# dram.net
KiCad netlist of a schematic drawn in Altium Designer
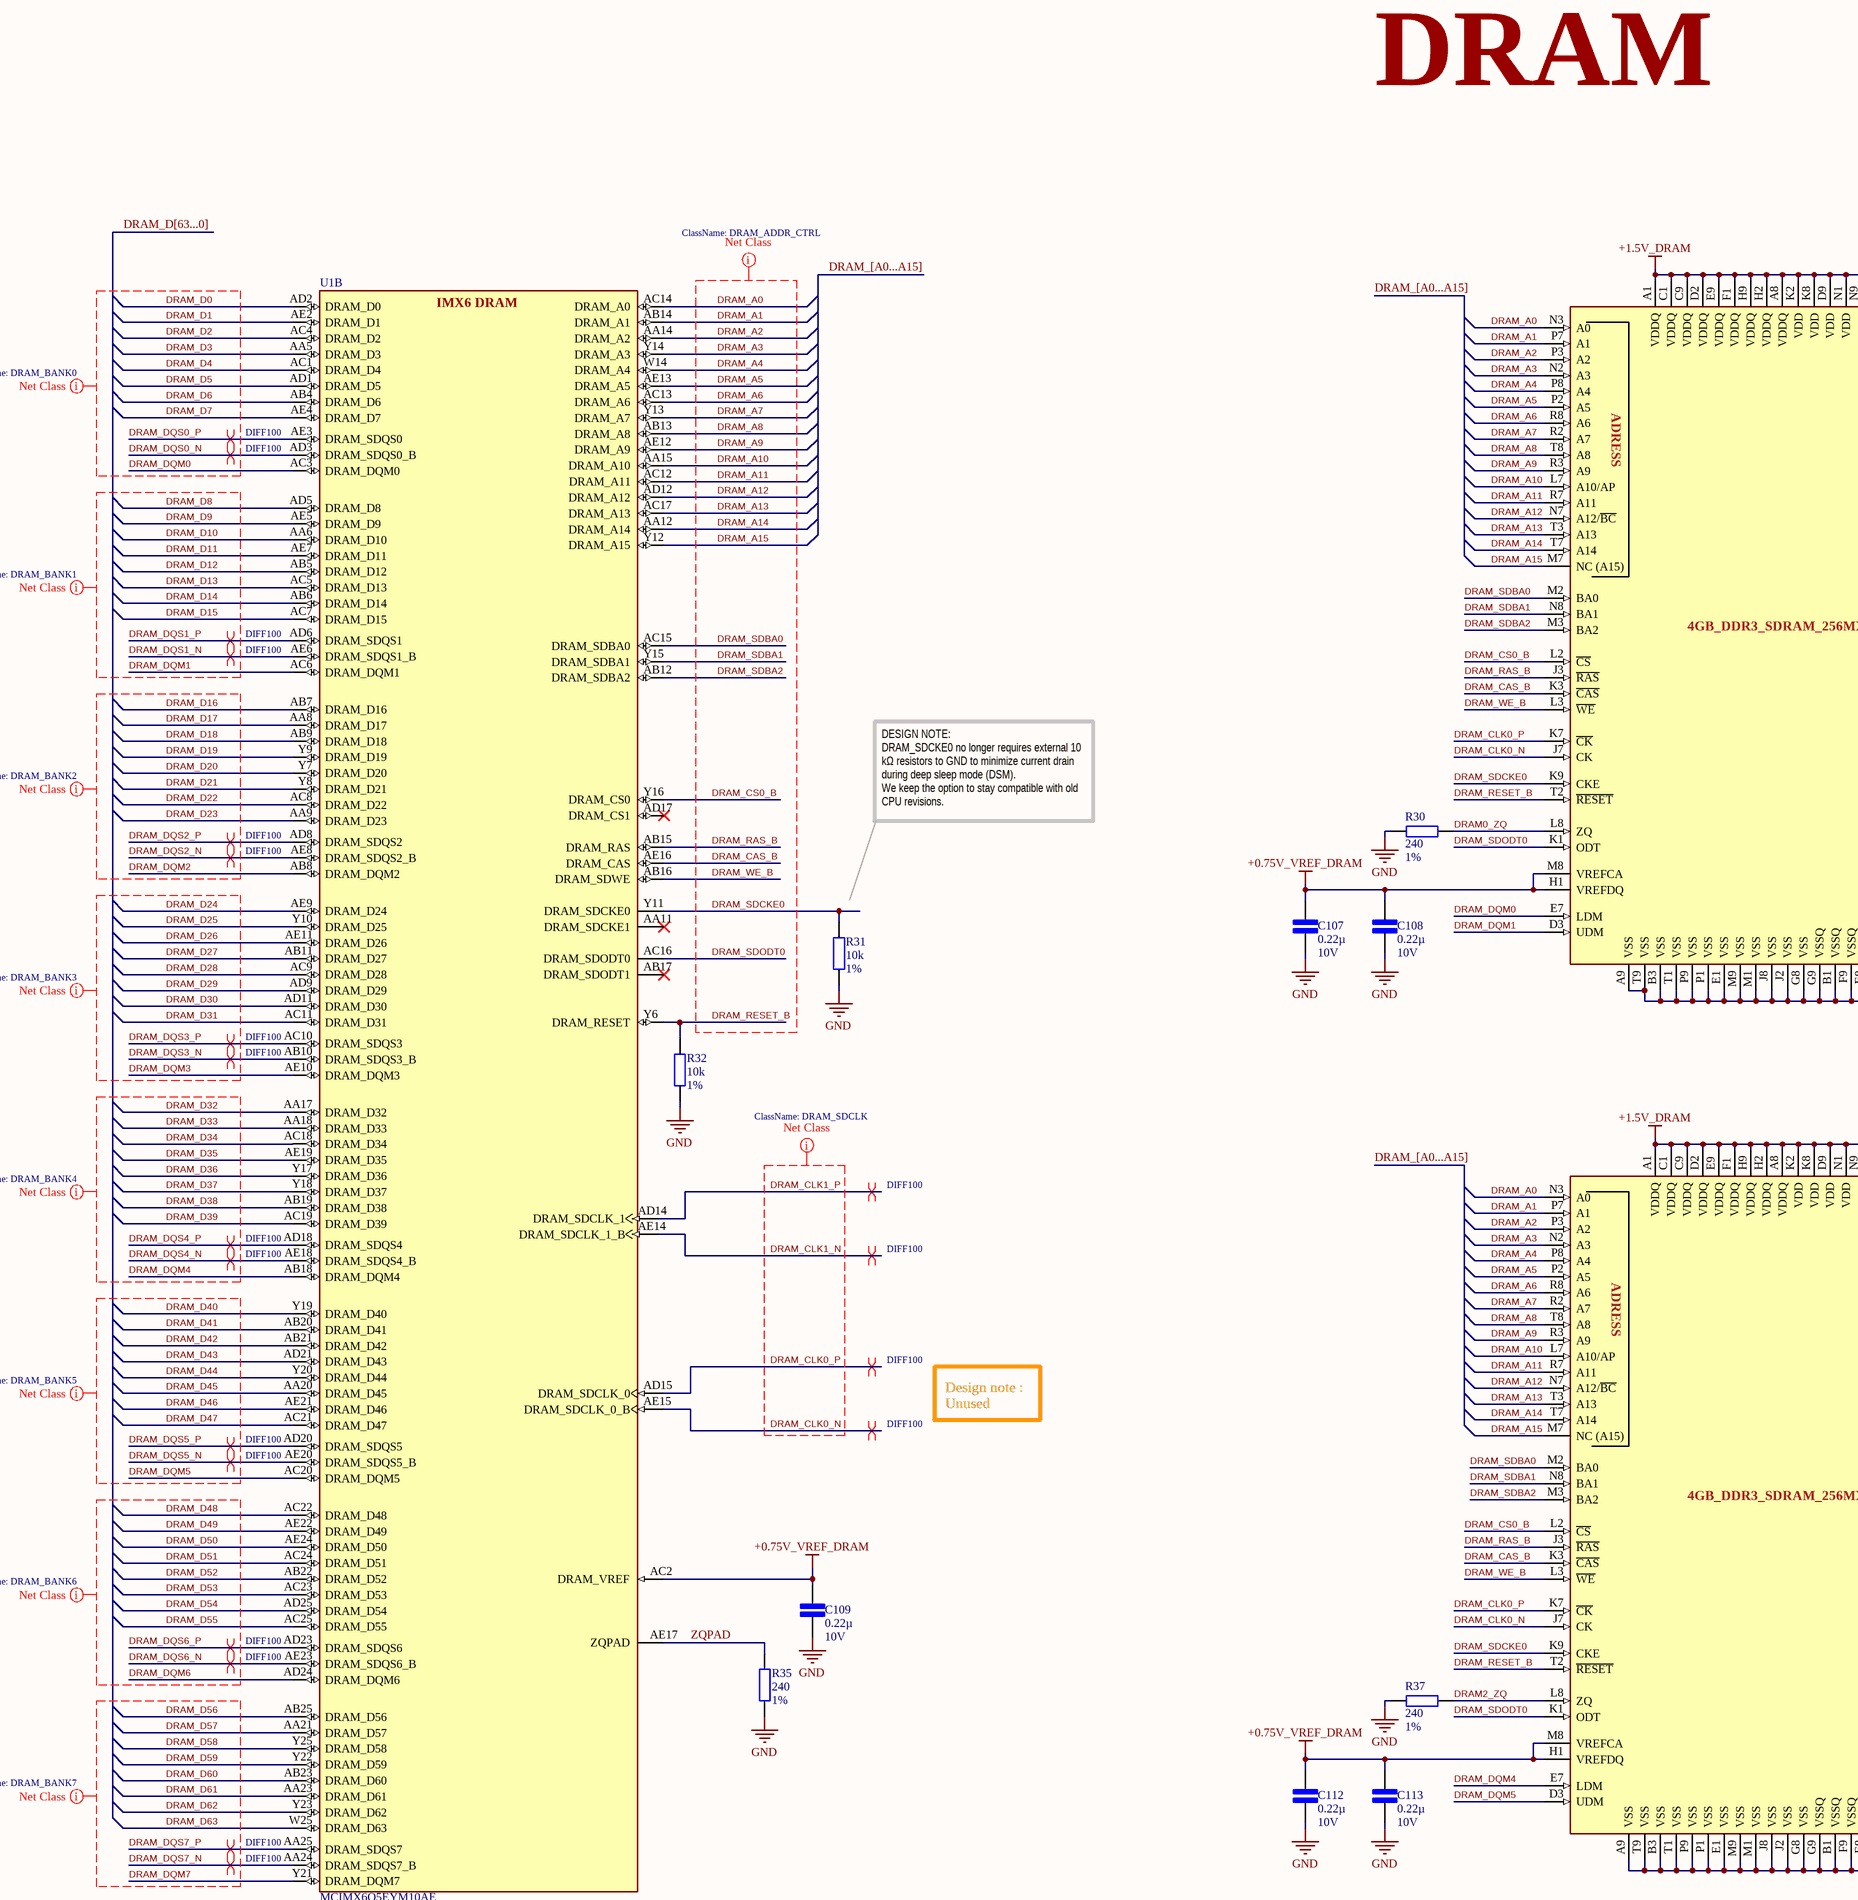
[diagram p0: dram.SchDoc, top left]
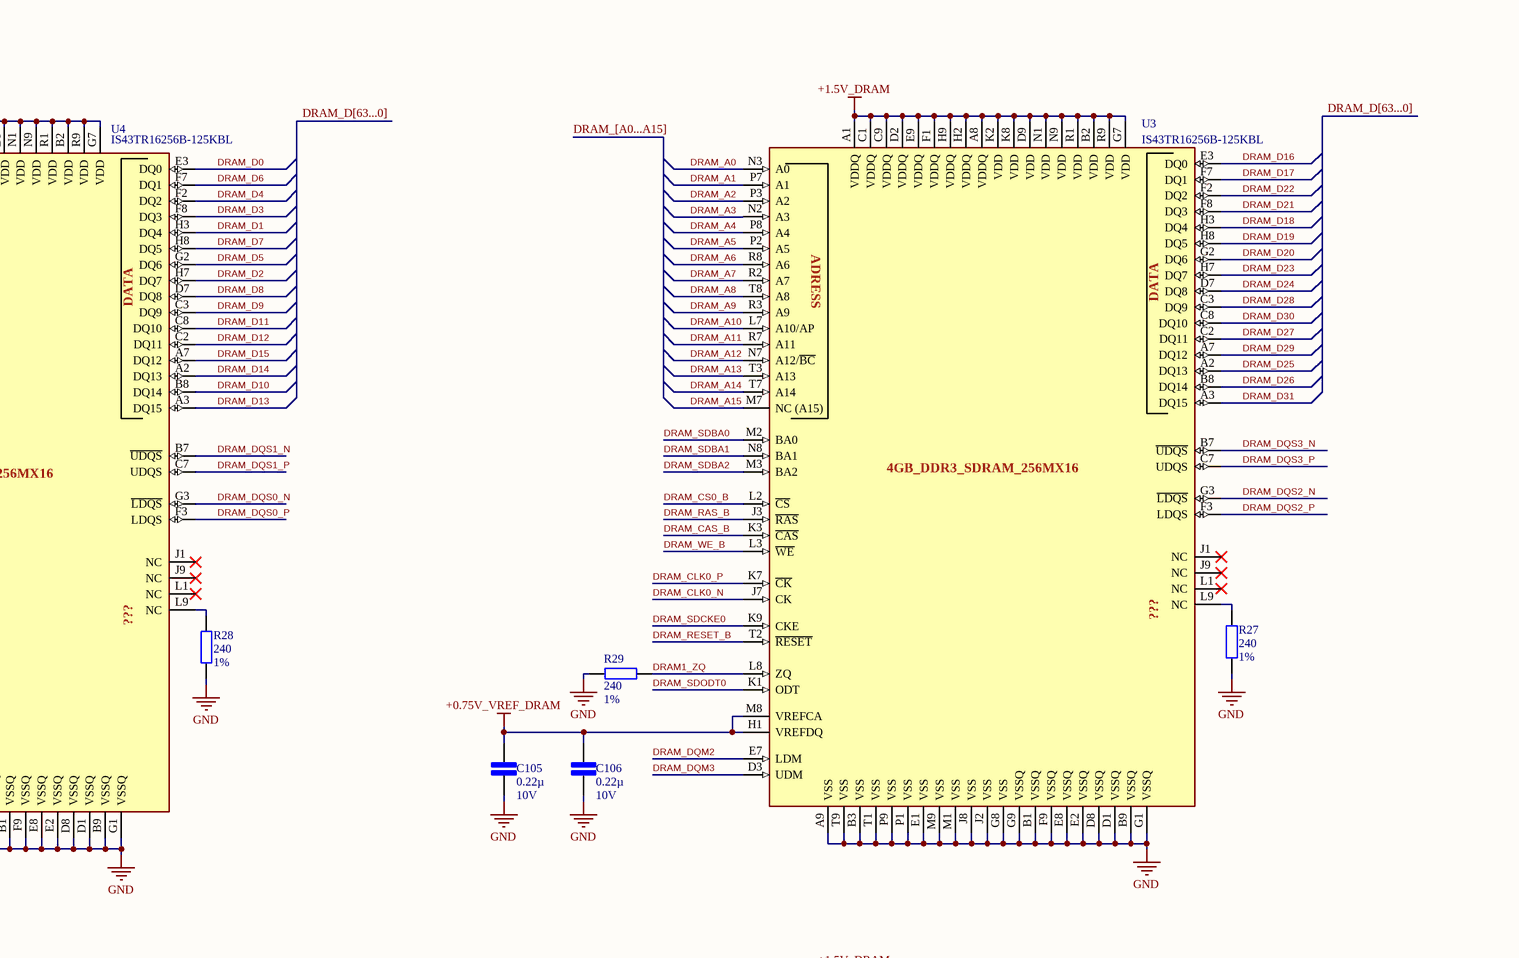
[diagram p1: dram.SchDoc, top right]
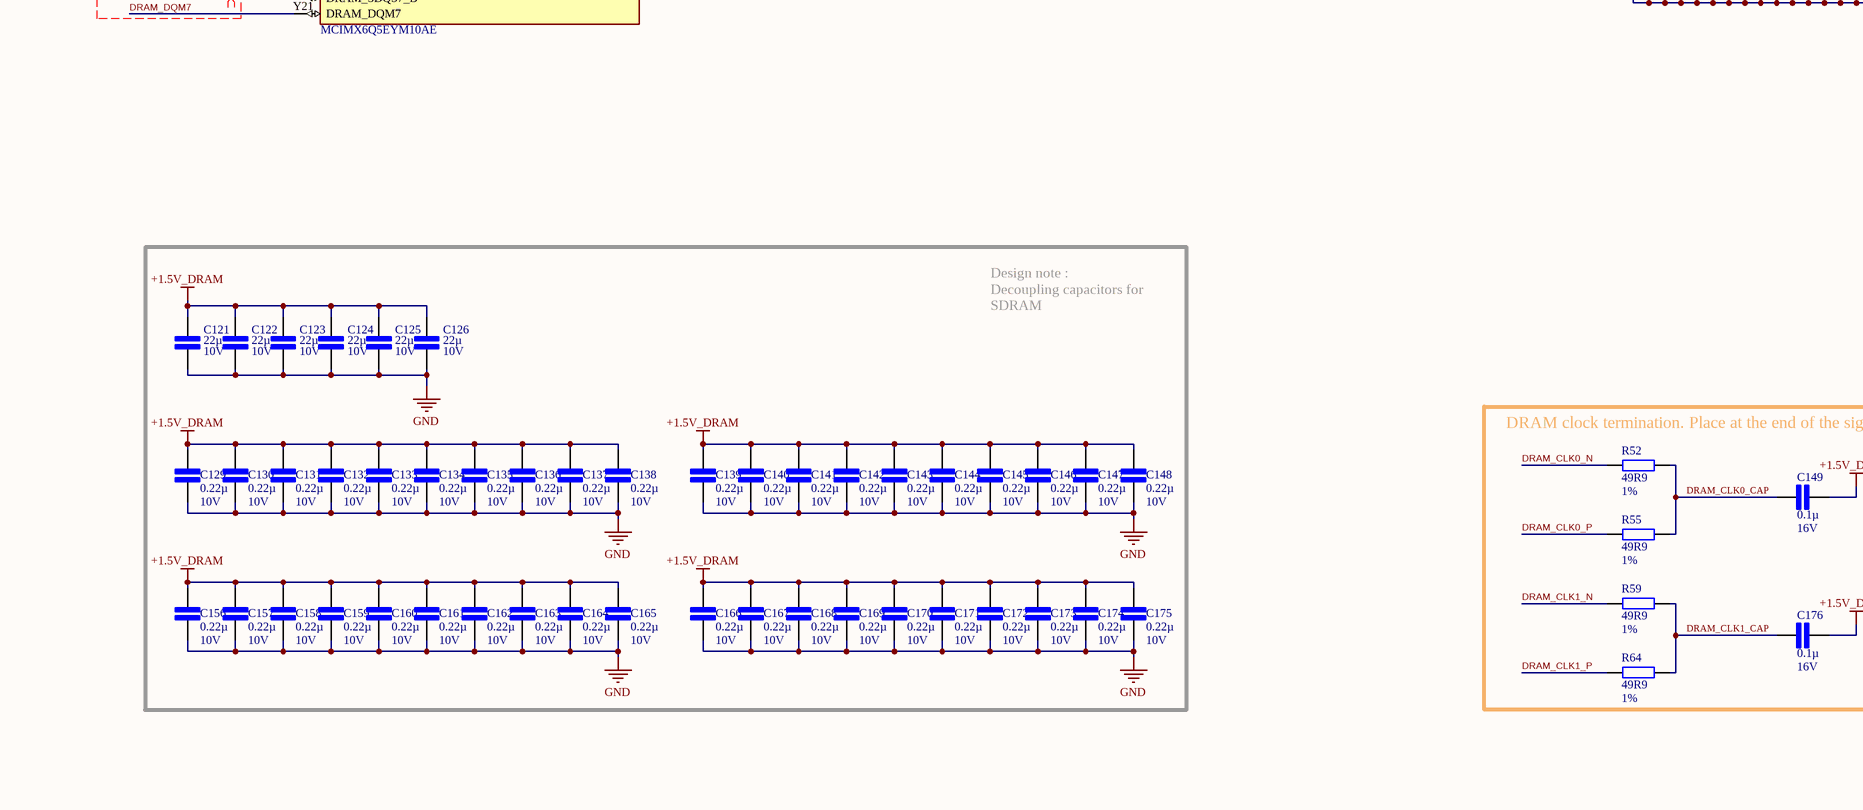
[diagram p2: dram.SchDoc, bottom left]
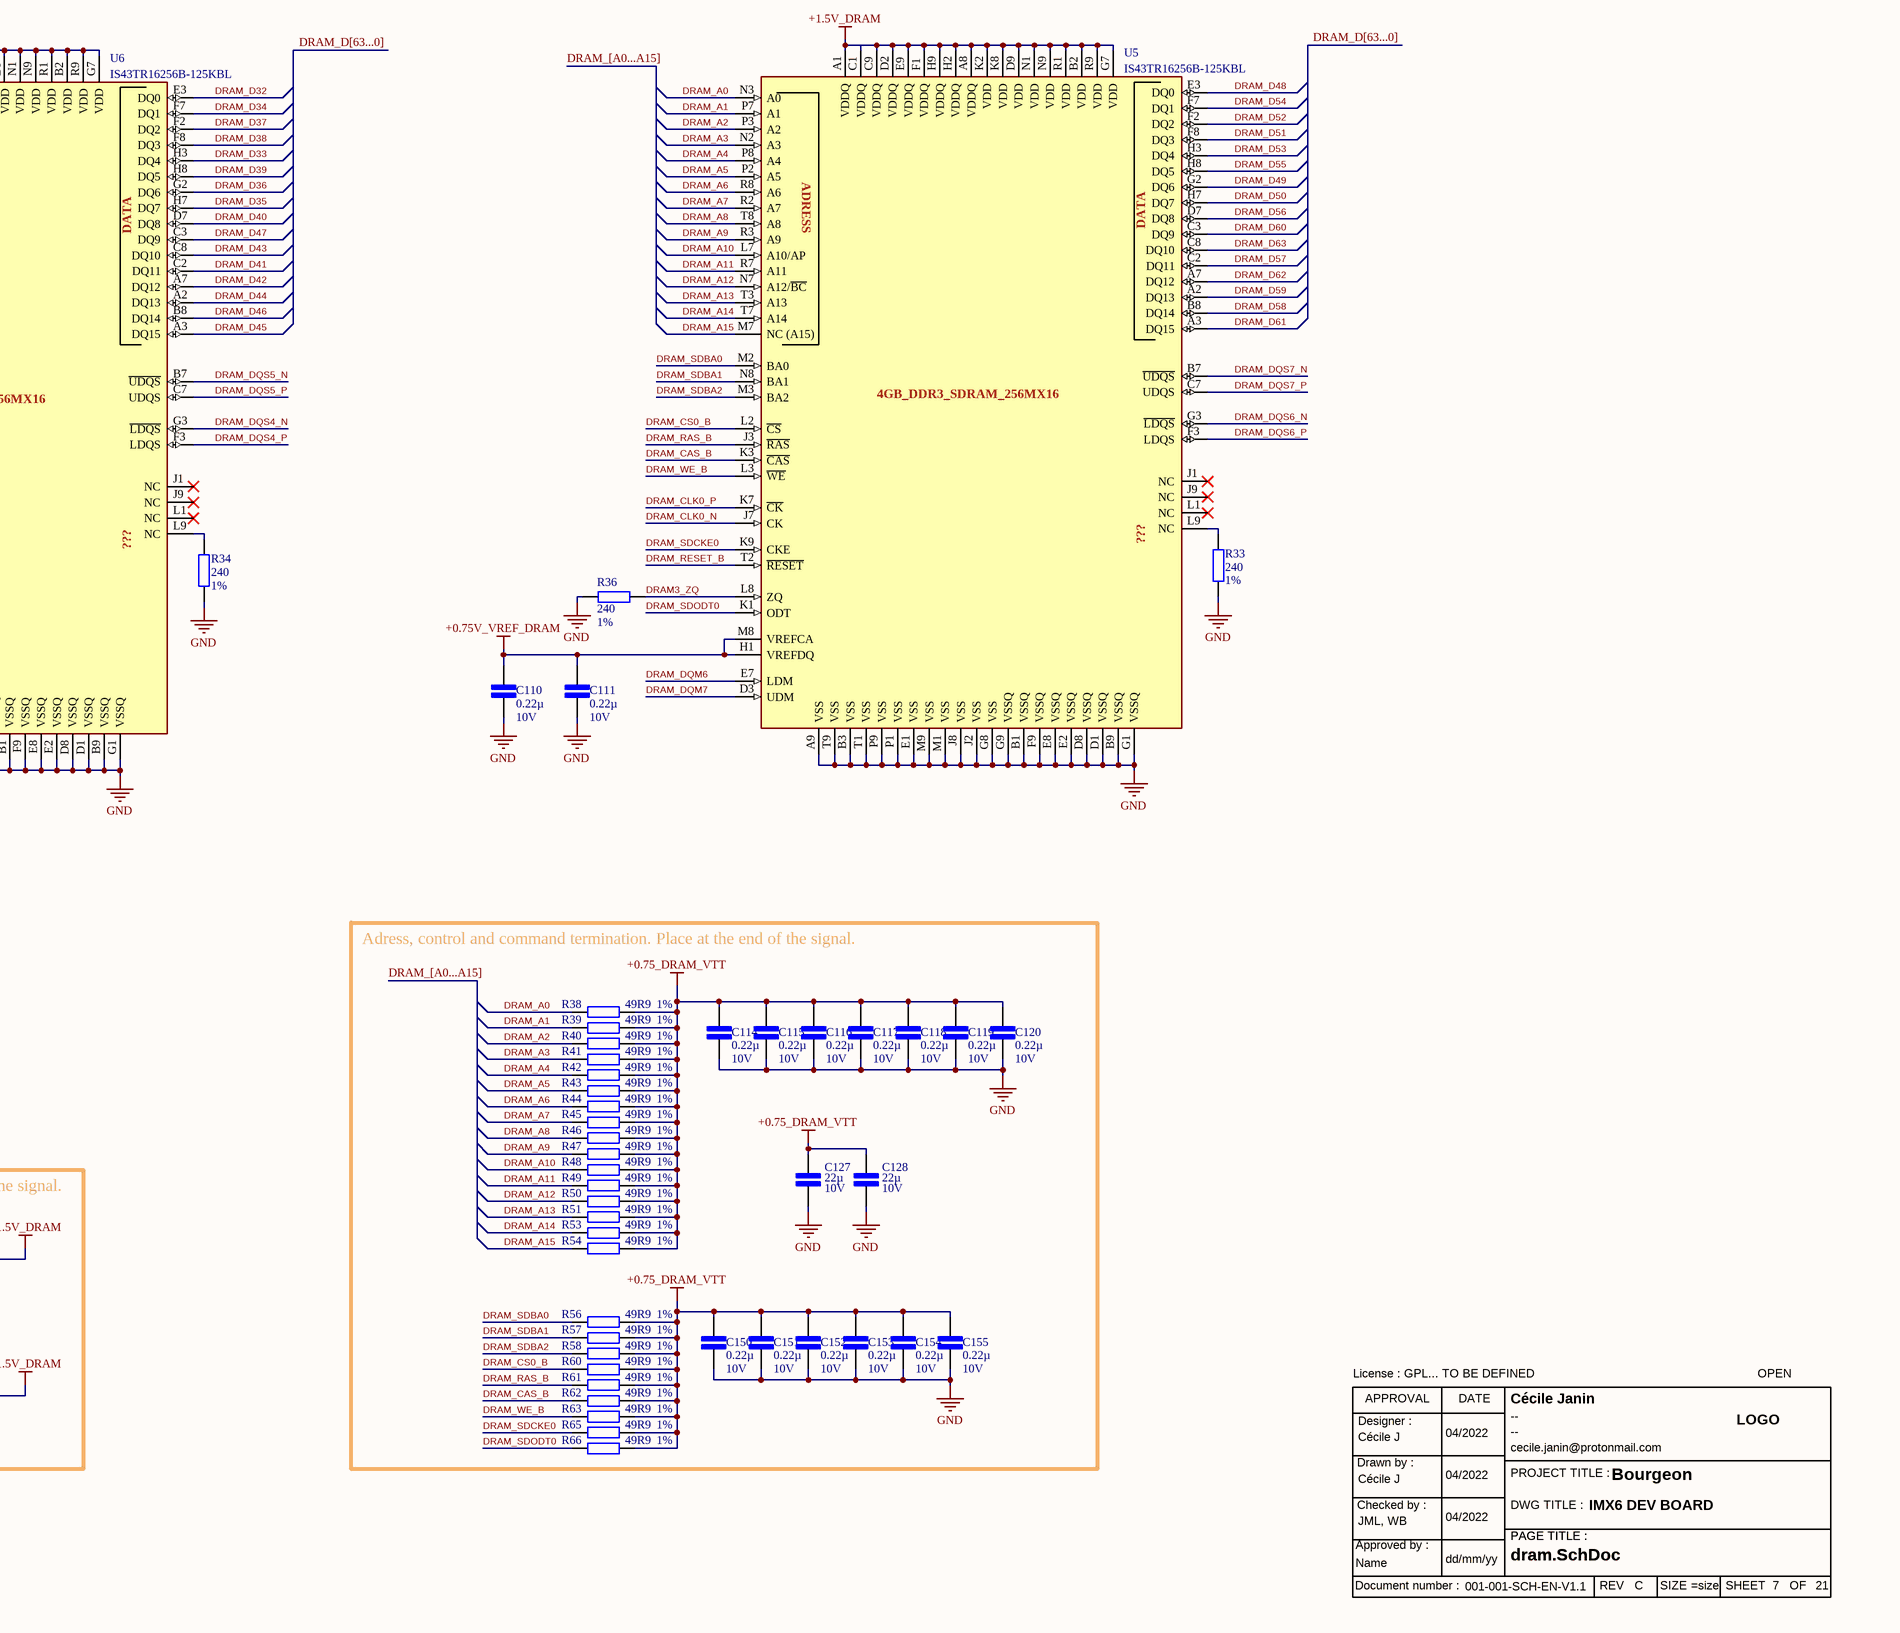
[diagram p3: dram.SchDoc, bottom right]

(export (version "E")
  (design (tool "Eeschema 10.0.6"))
  (components
    (comp (ref "C105")
      (value "0.22µ")
      (footprint "Cap cer 0402/1005")
      (description "cap cer 0.22µ 10V 10% X5R 0402")
      (fields (field (name "TENSION DU DIÉLECTRIQUE") "10V"))
      (libsource (lib "First Board IMX6") (part "cap 0.22µ 10V"))
    )
    (comp (ref "C106")
      (value "0.22µ")
      (footprint "Cap cer 0402/1005")
      (description "cap cer 0.22µ 10V 10% X5R 0402")
      (fields (field (name "TENSION DU DIÉLECTRIQUE") "10V"))
      (libsource (lib "First Board IMX6") (part "cap 0.22µ 10V"))
    )
    (comp (ref "C107")
      (value "0.22µ")
      (footprint "Cap cer 0402/1005")
      (description "cap cer 0.22µ 10V 10% X5R 0402")
      (fields (field (name "TENSION DU DIÉLECTRIQUE") "10V"))
      (libsource (lib "First Board IMX6") (part "cap 0.22µ 10V"))
    )
    (comp (ref "C108")
      (value "0.22µ")
      (footprint "Cap cer 0402/1005")
      (description "cap cer 0.22µ 10V 10% X5R 0402")
      (fields (field (name "TENSION DU DIÉLECTRIQUE") "10V"))
      (libsource (lib "First Board IMX6") (part "cap 0.22µ 10V"))
    )
    (comp (ref "C109")
      (value "0.22µ")
      (footprint "Cap cer 0402/1005")
      (description "cap cer 0.22µ 10V 10% X5R 0402")
      (fields (field (name "TENSION DU DIÉLECTRIQUE") "10V"))
      (libsource (lib "First Board IMX6") (part "cap 0.22µ 10V"))
    )
    (comp (ref "C110")
      (value "0.22µ")
      (footprint "Cap cer 0402/1005")
      (description "cap cer 0.22µ 10V 10% X5R 0402")
      (fields (field (name "TENSION DU DIÉLECTRIQUE") "10V"))
      (libsource (lib "First Board IMX6") (part "cap 0.22µ 10V"))
    )
    (comp (ref "C111")
      (value "0.22µ")
      (footprint "Cap cer 0402/1005")
      (description "cap cer 0.22µ 10V 10% X5R 0402")
      (fields (field (name "TENSION DU DIÉLECTRIQUE") "10V"))
      (libsource (lib "First Board IMX6") (part "cap 0.22µ 10V"))
    )
    (comp (ref "C112")
      (value "0.22µ")
      (footprint "Cap cer 0402/1005")
      (description "cap cer 0.22µ 10V 10% X5R 0402")
      (fields (field (name "TENSION DU DIÉLECTRIQUE") "10V"))
      (libsource (lib "First Board IMX6") (part "cap 0.22µ 10V"))
    )
    (comp (ref "C113")
      (value "0.22µ")
      (footprint "Cap cer 0402/1005")
      (description "cap cer 0.22µ 10V 10% X5R 0402")
      (fields (field (name "TENSION DU DIÉLECTRIQUE") "10V"))
      (libsource (lib "First Board IMX6") (part "cap 0.22µ 10V"))
    )
    (comp (ref "C114")
      (value "0.22µ")
      (footprint "Cap cer 0402/1005")
      (description "cap cer 0.22µ 10V 10% X5R 0402")
      (fields (field (name "TENSION DU DIÉLECTRIQUE") "10V"))
      (libsource (lib "First Board IMX6") (part "cap 0.22µ 10V"))
    )
    (comp (ref "C115")
      (value "0.22µ")
      (footprint "Cap cer 0402/1005")
      (description "cap cer 0.22µ 10V 10% X5R 0402")
      (fields (field (name "TENSION DU DIÉLECTRIQUE") "10V"))
      (libsource (lib "First Board IMX6") (part "cap 0.22µ 10V"))
    )
    (comp (ref "C116")
      (value "0.22µ")
      (footprint "Cap cer 0402/1005")
      (description "cap cer 0.22µ 10V 10% X5R 0402")
      (fields (field (name "TENSION DU DIÉLECTRIQUE") "10V"))
      (libsource (lib "First Board IMX6") (part "cap 0.22µ 10V"))
    )
    (comp (ref "C117")
      (value "0.22µ")
      (footprint "Cap cer 0402/1005")
      (description "cap cer 0.22µ 10V 10% X5R 0402")
      (fields (field (name "TENSION DU DIÉLECTRIQUE") "10V"))
      (libsource (lib "First Board IMX6") (part "cap 0.22µ 10V"))
    )
    (comp (ref "C118")
      (value "0.22µ")
      (footprint "Cap cer 0402/1005")
      (description "cap cer 0.22µ 10V 10% X5R 0402")
      (fields (field (name "TENSION DU DIÉLECTRIQUE") "10V"))
      (libsource (lib "First Board IMX6") (part "cap 0.22µ 10V"))
    )
    (comp (ref "C119")
      (value "0.22µ")
      (footprint "Cap cer 0402/1005")
      (description "cap cer 0.22µ 10V 10% X5R 0402")
      (fields (field (name "TENSION DU DIÉLECTRIQUE") "10V"))
      (libsource (lib "First Board IMX6") (part "cap 0.22µ 10V"))
    )
    (comp (ref "C120")
      (value "0.22µ")
      (footprint "Cap cer 0402/1005")
      (description "cap cer 0.22µ 10V 10% X5R 0402")
      (fields (field (name "TENSION DU DIÉLECTRIQUE") "10V"))
      (libsource (lib "First Board IMX6") (part "cap 0.22µ 10V"))
    )
    (comp (ref "C121")
      (value "22µ")
      (footprint "Cap cer 0603/4608")
      (description "cap cer 22µ 10V 10% X5R 0603")
      (fields (field (name "TENSION DU DIÉLECTRIQUE") "10V"))
      (libsource (lib "First Board IMX6") (part "cap 22µ 10V"))
    )
    (comp (ref "C122")
      (value "22µ")
      (footprint "Cap cer 0603/4608")
      (description "cap cer 22µ 10V 10% X5R 0603")
      (fields (field (name "TENSION DU DIÉLECTRIQUE") "10V"))
      (libsource (lib "First Board IMX6") (part "cap 22µ 10V"))
    )
    (comp (ref "C123")
      (value "22µ")
      (footprint "Cap cer 0603/4608")
      (description "cap cer 22µ 10V 10% X5R 0603")
      (fields (field (name "TENSION DU DIÉLECTRIQUE") "10V"))
      (libsource (lib "First Board IMX6") (part "cap 22µ 10V"))
    )
    (comp (ref "C124")
      (value "22µ")
      (footprint "Cap cer 0603/4608")
      (description "cap cer 22µ 10V 10% X5R 0603")
      (fields (field (name "TENSION DU DIÉLECTRIQUE") "10V"))
      (libsource (lib "First Board IMX6") (part "cap 22µ 10V"))
    )
    (comp (ref "C125")
      (value "22µ")
      (footprint "Cap cer 0603/4608")
      (description "cap cer 22µ 10V 10% X5R 0603")
      (fields (field (name "TENSION DU DIÉLECTRIQUE") "10V"))
      (libsource (lib "First Board IMX6") (part "cap 22µ 10V"))
    )
    (comp (ref "C126")
      (value "22µ")
      (footprint "Cap cer 0603/4608")
      (description "cap cer 22µ 10V 10% X5R 0603")
      (fields (field (name "TENSION DU DIÉLECTRIQUE") "10V"))
      (libsource (lib "First Board IMX6") (part "cap 22µ 10V"))
    )
    (comp (ref "C127")
      (value "22µ")
      (footprint "Cap cer 0603/4608")
      (description "cap cer 22µ 10V 10% X5R 0603")
      (fields (field (name "TENSION DU DIÉLECTRIQUE") "10V"))
      (libsource (lib "First Board IMX6") (part "cap 22µ 10V"))
    )
    (comp (ref "C128")
      (value "22µ")
      (footprint "Cap cer 0603/4608")
      (description "cap cer 22µ 10V 10% X5R 0603")
      (fields (field (name "TENSION DU DIÉLECTRIQUE") "10V"))
      (libsource (lib "First Board IMX6") (part "cap 22µ 10V"))
    )
    (comp (ref "C129")
      (value "0.22µ")
      (footprint "Cap cer 0402/1005")
      (description "cap cer 0.22µ 10V 10% X5R 0402")
      (fields (field (name "TENSION DU DIÉLECTRIQUE") "10V"))
      (libsource (lib "First Board IMX6") (part "cap 0.22µ 10V"))
    )
    (comp (ref "C130")
      (value "0.22µ")
      (footprint "Cap cer 0402/1005")
      (description "cap cer 0.22µ 10V 10% X5R 0402")
      (fields (field (name "TENSION DU DIÉLECTRIQUE") "10V"))
      (libsource (lib "First Board IMX6") (part "cap 0.22µ 10V"))
    )
    (comp (ref "C131")
      (value "0.22µ")
      (footprint "Cap cer 0402/1005")
      (description "cap cer 0.22µ 10V 10% X5R 0402")
      (fields (field (name "TENSION DU DIÉLECTRIQUE") "10V"))
      (libsource (lib "First Board IMX6") (part "cap 0.22µ 10V"))
    )
    (comp (ref "C132")
      (value "0.22µ")
      (footprint "Cap cer 0402/1005")
      (description "cap cer 0.22µ 10V 10% X5R 0402")
      (fields (field (name "TENSION DU DIÉLECTRIQUE") "10V"))
      (libsource (lib "First Board IMX6") (part "cap 0.22µ 10V"))
    )
    (comp (ref "C133")
      (value "0.22µ")
      (footprint "Cap cer 0402/1005")
      (description "cap cer 0.22µ 10V 10% X5R 0402")
      (fields (field (name "TENSION DU DIÉLECTRIQUE") "10V"))
      (libsource (lib "First Board IMX6") (part "cap 0.22µ 10V"))
    )
    (comp (ref "C134")
      (value "0.22µ")
      (footprint "Cap cer 0402/1005")
      (description "cap cer 0.22µ 10V 10% X5R 0402")
      (fields (field (name "TENSION DU DIÉLECTRIQUE") "10V"))
      (libsource (lib "First Board IMX6") (part "cap 0.22µ 10V"))
    )
    (comp (ref "C135")
      (value "0.22µ")
      (footprint "Cap cer 0402/1005")
      (description "cap cer 0.22µ 10V 10% X5R 0402")
      (fields (field (name "TENSION DU DIÉLECTRIQUE") "10V"))
      (libsource (lib "First Board IMX6") (part "cap 0.22µ 10V"))
    )
    (comp (ref "C136")
      (value "0.22µ")
      (footprint "Cap cer 0402/1005")
      (description "cap cer 0.22µ 10V 10% X5R 0402")
      (fields (field (name "TENSION DU DIÉLECTRIQUE") "10V"))
      (libsource (lib "First Board IMX6") (part "cap 0.22µ 10V"))
    )
    (comp (ref "C137")
      (value "0.22µ")
      (footprint "Cap cer 0402/1005")
      (description "cap cer 0.22µ 10V 10% X5R 0402")
      (fields (field (name "TENSION DU DIÉLECTRIQUE") "10V"))
      (libsource (lib "First Board IMX6") (part "cap 0.22µ 10V"))
    )
    (comp (ref "C138")
      (value "0.22µ")
      (footprint "Cap cer 0402/1005")
      (description "cap cer 0.22µ 10V 10% X5R 0402")
      (fields (field (name "TENSION DU DIÉLECTRIQUE") "10V"))
      (libsource (lib "First Board IMX6") (part "cap 0.22µ 10V"))
    )
    (comp (ref "C139")
      (value "0.22µ")
      (footprint "Cap cer 0402/1005")
      (description "cap cer 0.22µ 10V 10% X5R 0402")
      (fields (field (name "TENSION DU DIÉLECTRIQUE") "10V"))
      (libsource (lib "First Board IMX6") (part "cap 0.22µ 10V"))
    )
    (comp (ref "C140")
      (value "0.22µ")
      (footprint "Cap cer 0402/1005")
      (description "cap cer 0.22µ 10V 10% X5R 0402")
      (fields (field (name "TENSION DU DIÉLECTRIQUE") "10V"))
      (libsource (lib "First Board IMX6") (part "cap 0.22µ 10V"))
    )
    (comp (ref "C141")
      (value "0.22µ")
      (footprint "Cap cer 0402/1005")
      (description "cap cer 0.22µ 10V 10% X5R 0402")
      (fields (field (name "TENSION DU DIÉLECTRIQUE") "10V"))
      (libsource (lib "First Board IMX6") (part "cap 0.22µ 10V"))
    )
    (comp (ref "C142")
      (value "0.22µ")
      (footprint "Cap cer 0402/1005")
      (description "cap cer 0.22µ 10V 10% X5R 0402")
      (fields (field (name "TENSION DU DIÉLECTRIQUE") "10V"))
      (libsource (lib "First Board IMX6") (part "cap 0.22µ 10V"))
    )
    (comp (ref "C143")
      (value "0.22µ")
      (footprint "Cap cer 0402/1005")
      (description "cap cer 0.22µ 10V 10% X5R 0402")
      (fields (field (name "TENSION DU DIÉLECTRIQUE") "10V"))
      (libsource (lib "First Board IMX6") (part "cap 0.22µ 10V"))
    )
    (comp (ref "C144")
      (value "0.22µ")
      (footprint "Cap cer 0402/1005")
      (description "cap cer 0.22µ 10V 10% X5R 0402")
      (fields (field (name "TENSION DU DIÉLECTRIQUE") "10V"))
      (libsource (lib "First Board IMX6") (part "cap 0.22µ 10V"))
    )
    (comp (ref "C145")
      (value "0.22µ")
      (footprint "Cap cer 0402/1005")
      (description "cap cer 0.22µ 10V 10% X5R 0402")
      (fields (field (name "TENSION DU DIÉLECTRIQUE") "10V"))
      (libsource (lib "First Board IMX6") (part "cap 0.22µ 10V"))
    )
    (comp (ref "C146")
      (value "0.22µ")
      (footprint "Cap cer 0402/1005")
      (description "cap cer 0.22µ 10V 10% X5R 0402")
      (fields (field (name "TENSION DU DIÉLECTRIQUE") "10V"))
      (libsource (lib "First Board IMX6") (part "cap 0.22µ 10V"))
    )
    (comp (ref "C147")
      (value "0.22µ")
      (footprint "Cap cer 0402/1005")
      (description "cap cer 0.22µ 10V 10% X5R 0402")
      (fields (field (name "TENSION DU DIÉLECTRIQUE") "10V"))
      (libsource (lib "First Board IMX6") (part "cap 0.22µ 10V"))
    )
    (comp (ref "C148")
      (value "0.22µ")
      (footprint "Cap cer 0402/1005")
      (description "cap cer 0.22µ 10V 10% X5R 0402")
      (fields (field (name "TENSION DU DIÉLECTRIQUE") "10V"))
      (libsource (lib "First Board IMX6") (part "cap 0.22µ 10V"))
    )
    (comp (ref "C149")
      (value "0.1µ")
      (footprint "Cap cer 0402/1005")
      (description "cap solid electrolyte 0.1µ 6.3V 10%")
      (fields (field (name "TENSION DU DIÉLECTRIQUE") "16V"))
      (libsource (lib "First Board IMX6") (part "cap 0.1µ 16V"))
    )
    (comp (ref "C150")
      (value "0.22µ")
      (footprint "Cap cer 0402/1005")
      (description "cap cer 0.22µ 10V 10% X5R 0402")
      (fields (field (name "TENSION DU DIÉLECTRIQUE") "10V"))
      (libsource (lib "First Board IMX6") (part "cap 0.22µ 10V"))
    )
    (comp (ref "C151")
      (value "0.22µ")
      (footprint "Cap cer 0402/1005")
      (description "cap cer 0.22µ 10V 10% X5R 0402")
      (fields (field (name "TENSION DU DIÉLECTRIQUE") "10V"))
      (libsource (lib "First Board IMX6") (part "cap 0.22µ 10V"))
    )
    (comp (ref "C152")
      (value "0.22µ")
      (footprint "Cap cer 0402/1005")
      (description "cap cer 0.22µ 10V 10% X5R 0402")
      (fields (field (name "TENSION DU DIÉLECTRIQUE") "10V"))
      (libsource (lib "First Board IMX6") (part "cap 0.22µ 10V"))
    )
    (comp (ref "C153")
      (value "0.22µ")
      (footprint "Cap cer 0402/1005")
      (description "cap cer 0.22µ 10V 10% X5R 0402")
      (fields (field (name "TENSION DU DIÉLECTRIQUE") "10V"))
      (libsource (lib "First Board IMX6") (part "cap 0.22µ 10V"))
    )
    (comp (ref "C154")
      (value "0.22µ")
      (footprint "Cap cer 0402/1005")
      (description "cap cer 0.22µ 10V 10% X5R 0402")
      (fields (field (name "TENSION DU DIÉLECTRIQUE") "10V"))
      (libsource (lib "First Board IMX6") (part "cap 0.22µ 10V"))
    )
    (comp (ref "C155")
      (value "0.22µ")
      (footprint "Cap cer 0402/1005")
      (description "cap cer 0.22µ 10V 10% X5R 0402")
      (fields (field (name "TENSION DU DIÉLECTRIQUE") "10V"))
      (libsource (lib "First Board IMX6") (part "cap 0.22µ 10V"))
    )
    (comp (ref "C156")
      (value "0.22µ")
      (footprint "Cap cer 0402/1005")
      (description "cap cer 0.22µ 10V 10% X5R 0402")
      (fields (field (name "TENSION DU DIÉLECTRIQUE") "10V"))
      (libsource (lib "First Board IMX6") (part "cap 0.22µ 10V"))
    )
    (comp (ref "C157")
      (value "0.22µ")
      (footprint "Cap cer 0402/1005")
      (description "cap cer 0.22µ 10V 10% X5R 0402")
      (fields (field (name "TENSION DU DIÉLECTRIQUE") "10V"))
      (libsource (lib "First Board IMX6") (part "cap 0.22µ 10V"))
    )
    (comp (ref "C158")
      (value "0.22µ")
      (footprint "Cap cer 0402/1005")
      (description "cap cer 0.22µ 10V 10% X5R 0402")
      (fields (field (name "TENSION DU DIÉLECTRIQUE") "10V"))
      (libsource (lib "First Board IMX6") (part "cap 0.22µ 10V"))
    )
    (comp (ref "C159")
      (value "0.22µ")
      (footprint "Cap cer 0402/1005")
      (description "cap cer 0.22µ 10V 10% X5R 0402")
      (fields (field (name "TENSION DU DIÉLECTRIQUE") "10V"))
      (libsource (lib "First Board IMX6") (part "cap 0.22µ 10V"))
    )
    (comp (ref "C160")
      (value "0.22µ")
      (footprint "Cap cer 0402/1005")
      (description "cap cer 0.22µ 10V 10% X5R 0402")
      (fields (field (name "TENSION DU DIÉLECTRIQUE") "10V"))
      (libsource (lib "First Board IMX6") (part "cap 0.22µ 10V"))
    )
    (comp (ref "C161")
      (value "0.22µ")
      (footprint "Cap cer 0402/1005")
      (description "cap cer 0.22µ 10V 10% X5R 0402")
      (fields (field (name "TENSION DU DIÉLECTRIQUE") "10V"))
      (libsource (lib "First Board IMX6") (part "cap 0.22µ 10V"))
    )
    (comp (ref "C162")
      (value "0.22µ")
      (footprint "Cap cer 0402/1005")
      (description "cap cer 0.22µ 10V 10% X5R 0402")
      (fields (field (name "TENSION DU DIÉLECTRIQUE") "10V"))
      (libsource (lib "First Board IMX6") (part "cap 0.22µ 10V"))
    )
    (comp (ref "C163")
      (value "0.22µ")
      (footprint "Cap cer 0402/1005")
      (description "cap cer 0.22µ 10V 10% X5R 0402")
      (fields (field (name "TENSION DU DIÉLECTRIQUE") "10V"))
      (libsource (lib "First Board IMX6") (part "cap 0.22µ 10V"))
    )
    (comp (ref "C164")
      (value "0.22µ")
      (footprint "Cap cer 0402/1005")
      (description "cap cer 0.22µ 10V 10% X5R 0402")
      (fields (field (name "TENSION DU DIÉLECTRIQUE") "10V"))
      (libsource (lib "First Board IMX6") (part "cap 0.22µ 10V"))
    )
    (comp (ref "C165")
      (value "0.22µ")
      (footprint "Cap cer 0402/1005")
      (description "cap cer 0.22µ 10V 10% X5R 0402")
      (fields (field (name "TENSION DU DIÉLECTRIQUE") "10V"))
      (libsource (lib "First Board IMX6") (part "cap 0.22µ 10V"))
    )
    (comp (ref "C166")
      (value "0.22µ")
      (footprint "Cap cer 0402/1005")
      (description "cap cer 0.22µ 10V 10% X5R 0402")
      (fields (field (name "TENSION DU DIÉLECTRIQUE") "10V"))
      (libsource (lib "First Board IMX6") (part "cap 0.22µ 10V"))
    )
    (comp (ref "C167")
      (value "0.22µ")
      (footprint "Cap cer 0402/1005")
      (description "cap cer 0.22µ 10V 10% X5R 0402")
      (fields (field (name "TENSION DU DIÉLECTRIQUE") "10V"))
      (libsource (lib "First Board IMX6") (part "cap 0.22µ 10V"))
    )
    (comp (ref "C168")
      (value "0.22µ")
      (footprint "Cap cer 0402/1005")
      (description "cap cer 0.22µ 10V 10% X5R 0402")
      (fields (field (name "TENSION DU DIÉLECTRIQUE") "10V"))
      (libsource (lib "First Board IMX6") (part "cap 0.22µ 10V"))
    )
    (comp (ref "C169")
      (value "0.22µ")
      (footprint "Cap cer 0402/1005")
      (description "cap cer 0.22µ 10V 10% X5R 0402")
      (fields (field (name "TENSION DU DIÉLECTRIQUE") "10V"))
      (libsource (lib "First Board IMX6") (part "cap 0.22µ 10V"))
    )
    (comp (ref "C170")
      (value "0.22µ")
      (footprint "Cap cer 0402/1005")
      (description "cap cer 0.22µ 10V 10% X5R 0402")
      (fields (field (name "TENSION DU DIÉLECTRIQUE") "10V"))
      (libsource (lib "First Board IMX6") (part "cap 0.22µ 10V"))
    )
    (comp (ref "C171")
      (value "0.22µ")
      (footprint "Cap cer 0402/1005")
      (description "cap cer 0.22µ 10V 10% X5R 0402")
      (fields (field (name "TENSION DU DIÉLECTRIQUE") "10V"))
      (libsource (lib "First Board IMX6") (part "cap 0.22µ 10V"))
    )
    (comp (ref "C172")
      (value "0.22µ")
      (footprint "Cap cer 0402/1005")
      (description "cap cer 0.22µ 10V 10% X5R 0402")
      (fields (field (name "TENSION DU DIÉLECTRIQUE") "10V"))
      (libsource (lib "First Board IMX6") (part "cap 0.22µ 10V"))
    )
    (comp (ref "C173")
      (value "0.22µ")
      (footprint "Cap cer 0402/1005")
      (description "cap cer 0.22µ 10V 10% X5R 0402")
      (fields (field (name "TENSION DU DIÉLECTRIQUE") "10V"))
      (libsource (lib "First Board IMX6") (part "cap 0.22µ 10V"))
    )
    (comp (ref "C174")
      (value "0.22µ")
      (footprint "Cap cer 0402/1005")
      (description "cap cer 0.22µ 10V 10% X5R 0402")
      (fields (field (name "TENSION DU DIÉLECTRIQUE") "10V"))
      (libsource (lib "First Board IMX6") (part "cap 0.22µ 10V"))
    )
    (comp (ref "C175")
      (value "0.22µ")
      (footprint "Cap cer 0402/1005")
      (description "cap cer 0.22µ 10V 10% X5R 0402")
      (fields (field (name "TENSION DU DIÉLECTRIQUE") "10V"))
      (libsource (lib "First Board IMX6") (part "cap 0.22µ 10V"))
    )
    (comp (ref "C176")
      (value "0.1µ")
      (footprint "Cap cer 0402/1005")
      (description "cap solid electrolyte 0.1µ 6.3V 10%")
      (fields (field (name "TENSION DU DIÉLECTRIQUE") "16V"))
      (libsource (lib "First Board IMX6") (part "cap 0.1µ 16V"))
    )
    (comp (ref "R27")
      (value "240")
      (footprint "Res 0402/1005")
      (description "res 240 1% 0402")
      (fields (field (name "POURCENTAGE") "1%"))
      (libsource (lib "First Board IMX6") (part "res 240 1%"))
    )
    (comp (ref "R28")
      (value "240")
      (footprint "Res 0402/1005")
      (description "res 240 1% 0402")
      (fields (field (name "POURCENTAGE") "1%"))
      (libsource (lib "First Board IMX6") (part "res 240 1%"))
    )
    (comp (ref "R29")
      (value "240")
      (footprint "Res 0402/1005")
      (description "res 240 1% 0402")
      (fields (field (name "POURCENTAGE") "1%"))
      (libsource (lib "First Board IMX6") (part "res 240 1%"))
    )
    (comp (ref "R30")
      (value "240")
      (footprint "Res 0402/1005")
      (description "res 240 1% 0402")
      (fields (field (name "POURCENTAGE") "1%"))
      (libsource (lib "First Board IMX6") (part "res 240 1%"))
    )
    (comp (ref "R31")
      (value "10k")
      (footprint "Res 0402/1005")
      (description "res 10k 1% 0402")
      (fields (field (name "POURCENTAGE") "1%"))
      (libsource (lib "First Board IMX6") (part "res 10k 1%"))
    )
    (comp (ref "R32")
      (value "10k")
      (footprint "Res 0402/1005")
      (description "res 10k 1% 0402")
      (fields (field (name "POURCENTAGE") "1%"))
      (libsource (lib "First Board IMX6") (part "res 10k 1%"))
    )
    (comp (ref "R33")
      (value "240")
      (footprint "Res 0402/1005")
      (description "res 240 1% 0402")
      (fields (field (name "POURCENTAGE") "1%"))
      (libsource (lib "First Board IMX6") (part "res 240 1%"))
    )
    (comp (ref "R34")
      (value "240")
      (footprint "Res 0402/1005")
      (description "res 240 1% 0402")
      (fields (field (name "POURCENTAGE") "1%"))
      (libsource (lib "First Board IMX6") (part "res 240 1%"))
    )
    (comp (ref "R35")
      (value "240")
      (footprint "Res 0402/1005")
      (description "res 240 1% 0402")
      (fields (field (name "POURCENTAGE") "1%"))
      (libsource (lib "First Board IMX6") (part "res 240 1%"))
    )
    (comp (ref "R36")
      (value "240")
      (footprint "Res 0402/1005")
      (description "res 240 1% 0402")
      (fields (field (name "POURCENTAGE") "1%"))
      (libsource (lib "First Board IMX6") (part "res 240 1%"))
    )
    (comp (ref "R37")
      (value "240")
      (footprint "Res 0402/1005")
      (description "res 240 1% 0402")
      (fields (field (name "POURCENTAGE") "1%"))
      (libsource (lib "First Board IMX6") (part "res 240 1%"))
    )
    (comp (ref "R38")
      (value "49R9")
      (footprint "Res 0402/1005")
      (description "res 49R9 ohm 1% 0402")
      (fields (field (name "POURCENTAGE") "1%"))
      (libsource (lib "First Board IMX6") (part "res 49R9 1%"))
    )
    (comp (ref "R39")
      (value "49R9")
      (footprint "Res 0402/1005")
      (description "res 49R9 ohm 1% 0402")
      (fields (field (name "POURCENTAGE") "1%"))
      (libsource (lib "First Board IMX6") (part "res 49R9 1%"))
    )
    (comp (ref "R40")
      (value "49R9")
      (footprint "Res 0402/1005")
      (description "res 49R9 ohm 1% 0402")
      (fields (field (name "POURCENTAGE") "1%"))
      (libsource (lib "First Board IMX6") (part "res 49R9 1%"))
    )
    (comp (ref "R41")
      (value "49R9")
      (footprint "Res 0402/1005")
      (description "res 49R9 ohm 1% 0402")
      (fields (field (name "POURCENTAGE") "1%"))
      (libsource (lib "First Board IMX6") (part "res 49R9 1%"))
    )
    (comp (ref "R42")
      (value "49R9")
      (footprint "Res 0402/1005")
      (description "res 49R9 ohm 1% 0402")
      (fields (field (name "POURCENTAGE") "1%"))
      (libsource (lib "First Board IMX6") (part "res 49R9 1%"))
    )
    (comp (ref "R43")
      (value "49R9")
      (footprint "Res 0402/1005")
      (description "res 49R9 ohm 1% 0402")
      (fields (field (name "POURCENTAGE") "1%"))
      (libsource (lib "First Board IMX6") (part "res 49R9 1%"))
    )
    (comp (ref "R44")
      (value "49R9")
      (footprint "Res 0402/1005")
      (description "res 49R9 ohm 1% 0402")
      (fields (field (name "POURCENTAGE") "1%"))
      (libsource (lib "First Board IMX6") (part "res 49R9 1%"))
    )
    (comp (ref "R45")
      (value "49R9")
      (footprint "Res 0402/1005")
      (description "res 49R9 ohm 1% 0402")
      (fields (field (name "POURCENTAGE") "1%"))
      (libsource (lib "First Board IMX6") (part "res 49R9 1%"))
    )
    (comp (ref "R46")
      (value "49R9")
      (footprint "Res 0402/1005")
      (description "res 49R9 ohm 1% 0402")
      (fields (field (name "POURCENTAGE") "1%"))
      (libsource (lib "First Board IMX6") (part "res 49R9 1%"))
    )
    (comp (ref "R47")
      (value "49R9")
      (footprint "Res 0402/1005")
      (description "res 49R9 ohm 1% 0402")
      (fields (field (name "POURCENTAGE") "1%"))
      (libsource (lib "First Board IMX6") (part "res 49R9 1%"))
    )
    (comp (ref "R48")
      (value "49R9")
      (footprint "Res 0402/1005")
      (description "res 49R9 ohm 1% 0402")
      (fields (field (name "POURCENTAGE") "1%"))
      (libsource (lib "First Board IMX6") (part "res 49R9 1%"))
    )
    (comp (ref "R49")
      (value "49R9")
      (footprint "Res 0402/1005")
      (description "res 49R9 ohm 1% 0402")
      (fields (field (name "POURCENTAGE") "1%"))
      (libsource (lib "First Board IMX6") (part "res 49R9 1%"))
    )
    (comp (ref "R50")
      (value "49R9")
      (footprint "Res 0402/1005")
      (description "res 49R9 ohm 1% 0402")
      (fields (field (name "POURCENTAGE") "1%"))
      (libsource (lib "First Board IMX6") (part "res 49R9 1%"))
    )
    (comp (ref "R51")
      (value "49R9")
      (footprint "Res 0402/1005")
      (description "res 49R9 ohm 1% 0402")
      (fields (field (name "POURCENTAGE") "1%"))
      (libsource (lib "First Board IMX6") (part "res 49R9 1%"))
    )
    (comp (ref "R52")
      (value "49R9")
      (footprint "Res 0402/1005")
      (description "res 49R9 ohm 1% 0402")
      (fields (field (name "POURCENTAGE") "1%"))
      (libsource (lib "First Board IMX6") (part "res 49R9 1%"))
    )
    (comp (ref "R53")
      (value "49R9")
      (footprint "Res 0402/1005")
      (description "res 49R9 ohm 1% 0402")
      (fields (field (name "POURCENTAGE") "1%"))
      (libsource (lib "First Board IMX6") (part "res 49R9 1%"))
    )
    (comp (ref "R54")
      (value "49R9")
      (footprint "Res 0402/1005")
      (description "res 49R9 ohm 1% 0402")
      (fields (field (name "POURCENTAGE") "1%"))
      (libsource (lib "First Board IMX6") (part "res 49R9 1%"))
    )
    (comp (ref "R55")
      (value "49R9")
      (footprint "Res 0402/1005")
      (description "res 49R9 ohm 1% 0402")
      (fields (field (name "POURCENTAGE") "1%"))
      (libsource (lib "First Board IMX6") (part "res 49R9 1%"))
    )
    (comp (ref "R56")
      (value "49R9")
      (footprint "Res 0402/1005")
      (description "res 49R9 ohm 1% 0402")
      (fields (field (name "POURCENTAGE") "1%"))
      (libsource (lib "First Board IMX6") (part "res 49R9 1%"))
    )
    (comp (ref "R57")
      (value "49R9")
      (footprint "Res 0402/1005")
      (description "res 49R9 ohm 1% 0402")
      (fields (field (name "POURCENTAGE") "1%"))
      (libsource (lib "First Board IMX6") (part "res 49R9 1%"))
    )
    (comp (ref "R58")
      (value "49R9")
      (footprint "Res 0402/1005")
      (description "res 49R9 ohm 1% 0402")
      (fields (field (name "POURCENTAGE") "1%"))
      (libsource (lib "First Board IMX6") (part "res 49R9 1%"))
    )
    (comp (ref "R59")
      (value "49R9")
      (footprint "Res 0402/1005")
      (description "res 49R9 ohm 1% 0402")
      (fields (field (name "POURCENTAGE") "1%"))
      (libsource (lib "First Board IMX6") (part "res 49R9 1%"))
    )
    (comp (ref "R60")
      (value "49R9")
      (footprint "Res 0402/1005")
      (description "res 49R9 ohm 1% 0402")
      (fields (field (name "POURCENTAGE") "1%"))
      (libsource (lib "First Board IMX6") (part "res 49R9 1%"))
    )
    (comp (ref "R61")
      (value "49R9")
      (footprint "Res 0402/1005")
      (description "res 49R9 ohm 1% 0402")
      (fields (field (name "POURCENTAGE") "1%"))
      (libsource (lib "First Board IMX6") (part "res 49R9 1%"))
    )
    (comp (ref "R62")
      (value "49R9")
      (footprint "Res 0402/1005")
      (description "res 49R9 ohm 1% 0402")
      (fields (field (name "POURCENTAGE") "1%"))
      (libsource (lib "First Board IMX6") (part "res 49R9 1%"))
    )
    (comp (ref "R63")
      (value "49R9")
      (footprint "Res 0402/1005")
      (description "res 49R9 ohm 1% 0402")
      (fields (field (name "POURCENTAGE") "1%"))
      (libsource (lib "First Board IMX6") (part "res 49R9 1%"))
    )
    (comp (ref "R64")
      (value "49R9")
      (footprint "Res 0402/1005")
      (description "res 49R9 ohm 1% 0402")
      (fields (field (name "POURCENTAGE") "1%"))
      (libsource (lib "First Board IMX6") (part "res 49R9 1%"))
    )
    (comp (ref "R65")
      (value "49R9")
      (footprint "Res 0402/1005")
      (description "res 49R9 ohm 1% 0402")
      (fields (field (name "POURCENTAGE") "1%"))
      (libsource (lib "First Board IMX6") (part "res 49R9 1%"))
    )
    (comp (ref "R66")
      (value "49R9")
      (footprint "Res 0402/1005")
      (description "res 49R9 ohm 1% 0402")
      (fields (field (name "POURCENTAGE") "1%"))
      (libsource (lib "First Board IMX6") (part "res 49R9 1%"))
    )
    (comp (ref "TB5")
      (value "Title bloc ANSI modified")
      (libsource (lib "First Board IMX6") (part "Title bloc ANSI"))
    )
    (comp (ref "U1")
      (value "MCIMX6Q5EYM10AE")
      (footprint "FRES-2197-01")
      (fields
        (field (name "PARTNUMBER") "MCIMX6Q5EYM10ACR")
        (field (name "MANUFACTURER") "Freescale Semiconductor")
      )
      (libsource (lib "First Board IMX6") (part "IMX6Q5EYM10AE"))
    )
    (comp (ref "U3")
      (value "IS43TR16256B-125KBL")
      (footprint "BGA-96 DDR3")
      (description "DDR3 4Gbx4")
      (libsource (lib "First Board IMX6") (part "DDR3"))
    )
    (comp (ref "U4")
      (value "IS43TR16256B-125KBL")
      (footprint "BGA-96 DDR3")
      (description "DDR3 4Gbx4")
      (libsource (lib "First Board IMX6") (part "DDR3"))
    )
    (comp (ref "U5")
      (value "IS43TR16256B-125KBL")
      (footprint "BGA-96 DDR3")
      (description "DDR3 4Gbx4")
      (libsource (lib "First Board IMX6") (part "DDR3"))
    )
    (comp (ref "U6")
      (value "IS43TR16256B-125KBL")
      (footprint "BGA-96 DDR3")
      (description "DDR3 4Gbx4")
      (libsource (lib "First Board IMX6") (part "DDR3"))
    )
  )
  (nets
    (net (code "3") (name "+0.75V_VREF_DRAM") (class "Default")
      (node (ref "C105") (pin "1") (pinfunction "3_1") (pintype "passive"))
      (node (ref "C106") (pin "1") (pinfunction "3_1") (pintype "passive"))
      (node (ref "C107") (pin "1") (pinfunction "3_1") (pintype "passive"))
      (node (ref "C108") (pin "1") (pinfunction "3_1") (pintype "passive"))
      (node (ref "C109") (pin "1") (pinfunction "3_1") (pintype "passive"))
      (node (ref "C110") (pin "1") (pinfunction "3_1") (pintype "passive"))
      (node (ref "C111") (pin "1") (pinfunction "3_1") (pintype "passive"))
      (node (ref "C112") (pin "1") (pinfunction "3_1") (pintype "passive"))
      (node (ref "C113") (pin "1") (pinfunction "3_1") (pintype "passive"))
      (node (ref "U1") (pin "AC2") (pinfunction "DRAM_VREF_AC2") (pintype "input"))
      (node (ref "U3") (pin "H1") (pinfunction "VREFDQ_H1") (pintype "power_in"))
      (node (ref "U3") (pin "M8") (pinfunction "VREFCA_M8") (pintype "power_in"))
      (node (ref "U4") (pin "H1") (pinfunction "VREFDQ_H1") (pintype "power_in"))
      (node (ref "U4") (pin "M8") (pinfunction "VREFCA_M8") (pintype "power_in"))
      (node (ref "U5") (pin "H1") (pinfunction "VREFDQ_H1") (pintype "power_in"))
      (node (ref "U5") (pin "M8") (pinfunction "VREFCA_M8") (pintype "power_in"))
      (node (ref "U6") (pin "H1") (pinfunction "VREFDQ_H1") (pintype "power_in"))
      (node (ref "U6") (pin "M8") (pinfunction "VREFCA_M8") (pintype "power_in"))
    )
    (net (code "4") (name "+0.75_DRAM_VTT") (class "Default")
      (node (ref "C114") (pin "1") (pinfunction "3_1") (pintype "passive"))
      (node (ref "C115") (pin "1") (pinfunction "3_1") (pintype "passive"))
      (node (ref "C116") (pin "1") (pinfunction "3_1") (pintype "passive"))
      (node (ref "C117") (pin "1") (pinfunction "3_1") (pintype "passive"))
      (node (ref "C118") (pin "1") (pinfunction "3_1") (pintype "passive"))
      (node (ref "C119") (pin "1") (pinfunction "3_1") (pintype "passive"))
      (node (ref "C120") (pin "1") (pinfunction "3_1") (pintype "passive"))
      (node (ref "C127") (pin "1") (pinfunction "3_1") (pintype "passive"))
      (node (ref "C128") (pin "1") (pinfunction "3_1") (pintype "passive"))
      (node (ref "C150") (pin "1") (pinfunction "3_1") (pintype "passive"))
      (node (ref "C151") (pin "1") (pinfunction "3_1") (pintype "passive"))
      (node (ref "C152") (pin "1") (pinfunction "3_1") (pintype "passive"))
      (node (ref "C153") (pin "1") (pinfunction "3_1") (pintype "passive"))
      (node (ref "C154") (pin "1") (pinfunction "3_1") (pintype "passive"))
      (node (ref "C155") (pin "1") (pinfunction "3_1") (pintype "passive"))
      (node (ref "R38") (pin "2") (pintype "passive"))
      (node (ref "R39") (pin "2") (pintype "passive"))
      (node (ref "R40") (pin "2") (pintype "passive"))
      (node (ref "R41") (pin "2") (pintype "passive"))
      (node (ref "R42") (pin "2") (pintype "passive"))
      (node (ref "R43") (pin "2") (pintype "passive"))
      (node (ref "R44") (pin "2") (pintype "passive"))
      (node (ref "R45") (pin "2") (pintype "passive"))
      (node (ref "R46") (pin "2") (pintype "passive"))
      (node (ref "R47") (pin "2") (pintype "passive"))
      (node (ref "R48") (pin "2") (pintype "passive"))
      (node (ref "R49") (pin "2") (pintype "passive"))
      (node (ref "R50") (pin "2") (pintype "passive"))
      (node (ref "R51") (pin "2") (pintype "passive"))
      (node (ref "R53") (pin "2") (pintype "passive"))
      (node (ref "R54") (pin "2") (pintype "passive"))
      (node (ref "R56") (pin "2") (pintype "passive"))
      (node (ref "R57") (pin "2") (pintype "passive"))
      (node (ref "R58") (pin "2") (pintype "passive"))
      (node (ref "R60") (pin "2") (pintype "passive"))
      (node (ref "R61") (pin "2") (pintype "passive"))
      (node (ref "R62") (pin "2") (pintype "passive"))
      (node (ref "R63") (pin "2") (pintype "passive"))
      (node (ref "R65") (pin "2") (pintype "passive"))
      (node (ref "R66") (pin "2") (pintype "passive"))
    )
    (net (code "5") (name "+1.5V_DRAM") (class "Default")
      (node (ref "C121") (pin "1") (pinfunction "3_1") (pintype "passive"))
      (node (ref "C122") (pin "1") (pinfunction "3_1") (pintype "passive"))
      (node (ref "C123") (pin "1") (pinfunction "3_1") (pintype "passive"))
      (node (ref "C124") (pin "1") (pinfunction "3_1") (pintype "passive"))
      (node (ref "C125") (pin "1") (pinfunction "3_1") (pintype "passive"))
      (node (ref "C126") (pin "1") (pinfunction "3_1") (pintype "passive"))
      (node (ref "C129") (pin "1") (pinfunction "3_1") (pintype "passive"))
      (node (ref "C130") (pin "1") (pinfunction "3_1") (pintype "passive"))
      (node (ref "C131") (pin "1") (pinfunction "3_1") (pintype "passive"))
      (node (ref "C132") (pin "1") (pinfunction "3_1") (pintype "passive"))
      (node (ref "C133") (pin "1") (pinfunction "3_1") (pintype "passive"))
      (node (ref "C134") (pin "1") (pinfunction "3_1") (pintype "passive"))
      (node (ref "C135") (pin "1") (pinfunction "3_1") (pintype "passive"))
      (node (ref "C136") (pin "1") (pinfunction "3_1") (pintype "passive"))
      (node (ref "C137") (pin "1") (pinfunction "3_1") (pintype "passive"))
      (node (ref "C138") (pin "1") (pinfunction "3_1") (pintype "passive"))
      (node (ref "C139") (pin "1") (pinfunction "3_1") (pintype "passive"))
      (node (ref "C140") (pin "1") (pinfunction "3_1") (pintype "passive"))
      (node (ref "C141") (pin "1") (pinfunction "3_1") (pintype "passive"))
      (node (ref "C142") (pin "1") (pinfunction "3_1") (pintype "passive"))
      (node (ref "C143") (pin "1") (pinfunction "3_1") (pintype "passive"))
      (node (ref "C144") (pin "1") (pinfunction "3_1") (pintype "passive"))
      (node (ref "C145") (pin "1") (pinfunction "3_1") (pintype "passive"))
      (node (ref "C146") (pin "1") (pinfunction "3_1") (pintype "passive"))
      (node (ref "C147") (pin "1") (pinfunction "3_1") (pintype "passive"))
      (node (ref "C148") (pin "1") (pinfunction "3_1") (pintype "passive"))
      (node (ref "C149") (pin "2") (pinfunction "4_2") (pintype "passive"))
      (node (ref "C156") (pin "1") (pinfunction "3_1") (pintype "passive"))
      (node (ref "C157") (pin "1") (pinfunction "3_1") (pintype "passive"))
      (node (ref "C158") (pin "1") (pinfunction "3_1") (pintype "passive"))
      (node (ref "C159") (pin "1") (pinfunction "3_1") (pintype "passive"))
      (node (ref "C160") (pin "1") (pinfunction "3_1") (pintype "passive"))
      (node (ref "C161") (pin "1") (pinfunction "3_1") (pintype "passive"))
      (node (ref "C162") (pin "1") (pinfunction "3_1") (pintype "passive"))
      (node (ref "C163") (pin "1") (pinfunction "3_1") (pintype "passive"))
      (node (ref "C164") (pin "1") (pinfunction "3_1") (pintype "passive"))
      (node (ref "C165") (pin "1") (pinfunction "3_1") (pintype "passive"))
      (node (ref "C166") (pin "1") (pinfunction "3_1") (pintype "passive"))
      (node (ref "C167") (pin "1") (pinfunction "3_1") (pintype "passive"))
      (node (ref "C168") (pin "1") (pinfunction "3_1") (pintype "passive"))
      (node (ref "C169") (pin "1") (pinfunction "3_1") (pintype "passive"))
      (node (ref "C170") (pin "1") (pinfunction "3_1") (pintype "passive"))
      (node (ref "C171") (pin "1") (pinfunction "3_1") (pintype "passive"))
      (node (ref "C172") (pin "1") (pinfunction "3_1") (pintype "passive"))
      (node (ref "C173") (pin "1") (pinfunction "3_1") (pintype "passive"))
      (node (ref "C174") (pin "1") (pinfunction "3_1") (pintype "passive"))
      (node (ref "C175") (pin "1") (pinfunction "3_1") (pintype "passive"))
      (node (ref "C176") (pin "2") (pinfunction "4_2") (pintype "passive"))
      (node (ref "U3") (pin "A1") (pinfunction "VDDQ_A1") (pintype "power_in"))
      (node (ref "U3") (pin "A8") (pinfunction "VDDQ_A8") (pintype "power_in"))
      (node (ref "U3") (pin "B2") (pinfunction "VDD_B2") (pintype "power_in"))
      (node (ref "U3") (pin "C1") (pinfunction "VDDQ_C1") (pintype "power_in"))
      (node (ref "U3") (pin "C9") (pinfunction "VDDQ_C9") (pintype "power_in"))
      (node (ref "U3") (pin "D2") (pinfunction "VDDQ_D2") (pintype "power_in"))
      (node (ref "U3") (pin "D9") (pinfunction "VDD_D9") (pintype "power_in"))
      (node (ref "U3") (pin "E9") (pinfunction "VDDQ_E9") (pintype "power_in"))
      (node (ref "U3") (pin "F1") (pinfunction "VDDQ_F1") (pintype "power_in"))
      (node (ref "U3") (pin "G7") (pinfunction "VDD_G7") (pintype "power_in"))
      (node (ref "U3") (pin "H2") (pinfunction "VDDQ_H2") (pintype "power_in"))
      (node (ref "U3") (pin "H9") (pinfunction "VDDQ_H9") (pintype "power_in"))
      (node (ref "U3") (pin "K2") (pinfunction "VDD_K2") (pintype "power_in"))
      (node (ref "U3") (pin "K8") (pinfunction "VDD_K8") (pintype "power_in"))
      (node (ref "U3") (pin "N1") (pinfunction "VDD_N1") (pintype "power_in"))
      (node (ref "U3") (pin "N9") (pinfunction "VDD_N9") (pintype "power_in"))
      (node (ref "U3") (pin "R1") (pinfunction "VDD_R1") (pintype "power_in"))
      (node (ref "U3") (pin "R9") (pinfunction "VDD_R9") (pintype "power_in"))
      (node (ref "U4") (pin "A1") (pinfunction "VDDQ_A1") (pintype "power_in"))
      (node (ref "U4") (pin "A8") (pinfunction "VDDQ_A8") (pintype "power_in"))
      (node (ref "U4") (pin "B2") (pinfunction "VDD_B2") (pintype "power_in"))
      (node (ref "U4") (pin "C1") (pinfunction "VDDQ_C1") (pintype "power_in"))
      (node (ref "U4") (pin "C9") (pinfunction "VDDQ_C9") (pintype "power_in"))
      (node (ref "U4") (pin "D2") (pinfunction "VDDQ_D2") (pintype "power_in"))
      (node (ref "U4") (pin "D9") (pinfunction "VDD_D9") (pintype "power_in"))
      (node (ref "U4") (pin "E9") (pinfunction "VDDQ_E9") (pintype "power_in"))
      (node (ref "U4") (pin "F1") (pinfunction "VDDQ_F1") (pintype "power_in"))
      (node (ref "U4") (pin "G7") (pinfunction "VDD_G7") (pintype "power_in"))
      (node (ref "U4") (pin "H2") (pinfunction "VDDQ_H2") (pintype "power_in"))
      (node (ref "U4") (pin "H9") (pinfunction "VDDQ_H9") (pintype "power_in"))
      (node (ref "U4") (pin "K2") (pinfunction "VDD_K2") (pintype "power_in"))
      (node (ref "U4") (pin "K8") (pinfunction "VDD_K8") (pintype "power_in"))
      (node (ref "U4") (pin "N1") (pinfunction "VDD_N1") (pintype "power_in"))
      (node (ref "U4") (pin "N9") (pinfunction "VDD_N9") (pintype "power_in"))
      (node (ref "U4") (pin "R1") (pinfunction "VDD_R1") (pintype "power_in"))
      (node (ref "U4") (pin "R9") (pinfunction "VDD_R9") (pintype "power_in"))
      (node (ref "U5") (pin "A1") (pinfunction "VDDQ_A1") (pintype "power_in"))
      (node (ref "U5") (pin "A8") (pinfunction "VDDQ_A8") (pintype "power_in"))
      (node (ref "U5") (pin "B2") (pinfunction "VDD_B2") (pintype "power_in"))
      (node (ref "U5") (pin "C1") (pinfunction "VDDQ_C1") (pintype "power_in"))
      (node (ref "U5") (pin "C9") (pinfunction "VDDQ_C9") (pintype "power_in"))
      (node (ref "U5") (pin "D2") (pinfunction "VDDQ_D2") (pintype "power_in"))
      (node (ref "U5") (pin "D9") (pinfunction "VDD_D9") (pintype "power_in"))
      (node (ref "U5") (pin "E9") (pinfunction "VDDQ_E9") (pintype "power_in"))
      (node (ref "U5") (pin "F1") (pinfunction "VDDQ_F1") (pintype "power_in"))
      (node (ref "U5") (pin "G7") (pinfunction "VDD_G7") (pintype "power_in"))
      (node (ref "U5") (pin "H2") (pinfunction "VDDQ_H2") (pintype "power_in"))
      (node (ref "U5") (pin "H9") (pinfunction "VDDQ_H9") (pintype "power_in"))
      (node (ref "U5") (pin "K2") (pinfunction "VDD_K2") (pintype "power_in"))
      (node (ref "U5") (pin "K8") (pinfunction "VDD_K8") (pintype "power_in"))
      (node (ref "U5") (pin "N1") (pinfunction "VDD_N1") (pintype "power_in"))
      (node (ref "U5") (pin "N9") (pinfunction "VDD_N9") (pintype "power_in"))
      (node (ref "U5") (pin "R1") (pinfunction "VDD_R1") (pintype "power_in"))
      (node (ref "U5") (pin "R9") (pinfunction "VDD_R9") (pintype "power_in"))
      (node (ref "U6") (pin "A1") (pinfunction "VDDQ_A1") (pintype "power_in"))
      (node (ref "U6") (pin "A8") (pinfunction "VDDQ_A8") (pintype "power_in"))
      (node (ref "U6") (pin "B2") (pinfunction "VDD_B2") (pintype "power_in"))
      (node (ref "U6") (pin "C1") (pinfunction "VDDQ_C1") (pintype "power_in"))
      (node (ref "U6") (pin "C9") (pinfunction "VDDQ_C9") (pintype "power_in"))
      (node (ref "U6") (pin "D2") (pinfunction "VDDQ_D2") (pintype "power_in"))
      (node (ref "U6") (pin "D9") (pinfunction "VDD_D9") (pintype "power_in"))
      (node (ref "U6") (pin "E9") (pinfunction "VDDQ_E9") (pintype "power_in"))
      (node (ref "U6") (pin "F1") (pinfunction "VDDQ_F1") (pintype "power_in"))
      (node (ref "U6") (pin "G7") (pinfunction "VDD_G7") (pintype "power_in"))
      (node (ref "U6") (pin "H2") (pinfunction "VDDQ_H2") (pintype "power_in"))
      (node (ref "U6") (pin "H9") (pinfunction "VDDQ_H9") (pintype "power_in"))
      (node (ref "U6") (pin "K2") (pinfunction "VDD_K2") (pintype "power_in"))
      (node (ref "U6") (pin "K8") (pinfunction "VDD_K8") (pintype "power_in"))
      (node (ref "U6") (pin "N1") (pinfunction "VDD_N1") (pintype "power_in"))
      (node (ref "U6") (pin "N9") (pinfunction "VDD_N9") (pintype "power_in"))
      (node (ref "U6") (pin "R1") (pinfunction "VDD_R1") (pintype "power_in"))
      (node (ref "U6") (pin "R9") (pinfunction "VDD_R9") (pintype "power_in"))
    )
    (net (code "6") (name "/DRAM0_ZQ") (class "Default")
      (node (ref "R30") (pin "2") (pintype "passive"))
      (node (ref "U4") (pin "L8") (pinfunction "ZQ_L8") (pintype "input"))
    )
    (net (code "7") (name "/DRAM1_ZQ") (class "Default")
      (node (ref "R29") (pin "2") (pintype "passive"))
      (node (ref "U3") (pin "L8") (pinfunction "ZQ_L8") (pintype "input"))
    )
    (net (code "8") (name "/DRAM2_ZQ") (class "Default")
      (node (ref "R37") (pin "2") (pintype "passive"))
      (node (ref "U6") (pin "L8") (pinfunction "ZQ_L8") (pintype "input"))
    )
    (net (code "9") (name "/DRAM3_ZQ") (class "Default")
      (node (ref "R36") (pin "2") (pintype "passive"))
      (node (ref "U5") (pin "L8") (pinfunction "ZQ_L8") (pintype "input"))
    )
    (net (code "10") (name "/DRAM_A0") (class "Default")
      (node (ref "R38") (pin "1") (pintype "passive"))
      (node (ref "U1") (pin "AC14") (pinfunction "DRAM_A0_AC14") (pintype "bidirectional"))
      (node (ref "U3") (pin "N3") (pinfunction "A0_N3") (pintype "input"))
      (node (ref "U4") (pin "N3") (pinfunction "A0_N3") (pintype "input"))
      (node (ref "U5") (pin "N3") (pinfunction "A0_N3") (pintype "input"))
      (node (ref "U6") (pin "N3") (pinfunction "A0_N3") (pintype "input"))
    )
    (net (code "11") (name "/DRAM_A1") (class "Default")
      (node (ref "R39") (pin "1") (pintype "passive"))
      (node (ref "U1") (pin "AB14") (pinfunction "DRAM_A1_AB14") (pintype "bidirectional"))
      (node (ref "U3") (pin "P7") (pinfunction "A1_P7") (pintype "input"))
      (node (ref "U4") (pin "P7") (pinfunction "A1_P7") (pintype "input"))
      (node (ref "U5") (pin "P7") (pinfunction "A1_P7") (pintype "input"))
      (node (ref "U6") (pin "P7") (pinfunction "A1_P7") (pintype "input"))
    )
    (net (code "12") (name "/DRAM_A2") (class "Default")
      (node (ref "R40") (pin "1") (pintype "passive"))
      (node (ref "U1") (pin "AA14") (pinfunction "DRAM_A2_AA14") (pintype "bidirectional"))
      (node (ref "U3") (pin "P3") (pinfunction "A2_P3") (pintype "input"))
      (node (ref "U4") (pin "P3") (pinfunction "A2_P3") (pintype "input"))
      (node (ref "U5") (pin "P3") (pinfunction "A2_P3") (pintype "input"))
      (node (ref "U6") (pin "P3") (pinfunction "A2_P3") (pintype "input"))
    )
    (net (code "13") (name "/DRAM_A3") (class "Default")
      (node (ref "R41") (pin "1") (pintype "passive"))
      (node (ref "U1") (pin "Y14") (pinfunction "DRAM_A3_Y14") (pintype "bidirectional"))
      (node (ref "U3") (pin "N2") (pinfunction "A3_N2") (pintype "input"))
      (node (ref "U4") (pin "N2") (pinfunction "A3_N2") (pintype "input"))
      (node (ref "U5") (pin "N2") (pinfunction "A3_N2") (pintype "input"))
      (node (ref "U6") (pin "N2") (pinfunction "A3_N2") (pintype "input"))
    )
    (net (code "14") (name "/DRAM_A4") (class "Default")
      (node (ref "R42") (pin "1") (pintype "passive"))
      (node (ref "U1") (pin "W14") (pinfunction "DRAM_A4_W14") (pintype "bidirectional"))
      (node (ref "U3") (pin "P8") (pinfunction "A4_P8") (pintype "input"))
      (node (ref "U4") (pin "P8") (pinfunction "A4_P8") (pintype "input"))
      (node (ref "U5") (pin "P8") (pinfunction "A4_P8") (pintype "input"))
      (node (ref "U6") (pin "P8") (pinfunction "A4_P8") (pintype "input"))
    )
    (net (code "15") (name "/DRAM_A5") (class "Default")
      (node (ref "R43") (pin "1") (pintype "passive"))
      (node (ref "U1") (pin "AE13") (pinfunction "DRAM_A5_AE13") (pintype "bidirectional"))
      (node (ref "U3") (pin "P2") (pinfunction "A5_P2") (pintype "input"))
      (node (ref "U4") (pin "P2") (pinfunction "A5_P2") (pintype "input"))
      (node (ref "U5") (pin "P2") (pinfunction "A5_P2") (pintype "input"))
      (node (ref "U6") (pin "P2") (pinfunction "A5_P2") (pintype "input"))
    )
    (net (code "16") (name "/DRAM_A6") (class "Default")
      (node (ref "R44") (pin "1") (pintype "passive"))
      (node (ref "U1") (pin "AC13") (pinfunction "DRAM_A6_AC13") (pintype "bidirectional"))
      (node (ref "U3") (pin "R8") (pinfunction "A6_R8") (pintype "input"))
      (node (ref "U4") (pin "R8") (pinfunction "A6_R8") (pintype "input"))
      (node (ref "U5") (pin "R8") (pinfunction "A6_R8") (pintype "input"))
      (node (ref "U6") (pin "R8") (pinfunction "A6_R8") (pintype "input"))
    )
    (net (code "17") (name "/DRAM_A7") (class "Default")
      (node (ref "R45") (pin "1") (pintype "passive"))
      (node (ref "U1") (pin "Y13") (pinfunction "DRAM_A7_Y13") (pintype "bidirectional"))
      (node (ref "U3") (pin "R2") (pinfunction "A7_R2") (pintype "input"))
      (node (ref "U4") (pin "R2") (pinfunction "A7_R2") (pintype "input"))
      (node (ref "U5") (pin "R2") (pinfunction "A7_R2") (pintype "input"))
      (node (ref "U6") (pin "R2") (pinfunction "A7_R2") (pintype "input"))
    )
    (net (code "18") (name "/DRAM_A8") (class "Default")
      (node (ref "R46") (pin "1") (pintype "passive"))
      (node (ref "U1") (pin "AB13") (pinfunction "DRAM_A8_AB13") (pintype "bidirectional"))
      (node (ref "U3") (pin "T8") (pinfunction "A8_T8") (pintype "input"))
      (node (ref "U4") (pin "T8") (pinfunction "A8_T8") (pintype "input"))
      (node (ref "U5") (pin "T8") (pinfunction "A8_T8") (pintype "input"))
      (node (ref "U6") (pin "T8") (pinfunction "A8_T8") (pintype "input"))
    )
    (net (code "19") (name "/DRAM_A9") (class "Default")
      (node (ref "R47") (pin "1") (pintype "passive"))
      (node (ref "U1") (pin "AE12") (pinfunction "DRAM_A9_AE12") (pintype "bidirectional"))
      (node (ref "U3") (pin "R3") (pinfunction "A9_R3") (pintype "input"))
      (node (ref "U4") (pin "R3") (pinfunction "A9_R3") (pintype "input"))
      (node (ref "U5") (pin "R3") (pinfunction "A9_R3") (pintype "input"))
      (node (ref "U6") (pin "R3") (pinfunction "A9_R3") (pintype "input"))
    )
    (net (code "20") (name "/DRAM_A10") (class "Default")
      (node (ref "R48") (pin "1") (pintype "passive"))
      (node (ref "U1") (pin "AA15") (pinfunction "DRAM_A10_AA15") (pintype "bidirectional"))
      (node (ref "U3") (pin "L7") (pinfunction "A10/AP_L7") (pintype "input"))
      (node (ref "U4") (pin "L7") (pinfunction "A10/AP_L7") (pintype "input"))
      (node (ref "U5") (pin "L7") (pinfunction "A10/AP_L7") (pintype "input"))
      (node (ref "U6") (pin "L7") (pinfunction "A10/AP_L7") (pintype "input"))
    )
    (net (code "21") (name "/DRAM_A11") (class "Default")
      (node (ref "R49") (pin "1") (pintype "passive"))
      (node (ref "U1") (pin "AC12") (pinfunction "DRAM_A11_AC12") (pintype "bidirectional"))
      (node (ref "U3") (pin "R7") (pinfunction "A11_R7") (pintype "input"))
      (node (ref "U4") (pin "R7") (pinfunction "A11_R7") (pintype "input"))
      (node (ref "U5") (pin "R7") (pinfunction "A11_R7") (pintype "input"))
      (node (ref "U6") (pin "R7") (pinfunction "A11_R7") (pintype "input"))
    )
    (net (code "22") (name "/DRAM_A12") (class "Default")
      (node (ref "R50") (pin "1") (pintype "passive"))
      (node (ref "U1") (pin "AD12") (pinfunction "DRAM_A12_AD12") (pintype "bidirectional"))
      (node (ref "U3") (pin "N7") (pinfunction "A12/~{BC}_N7") (pintype "input"))
      (node (ref "U4") (pin "N7") (pinfunction "A12/~{BC}_N7") (pintype "input"))
      (node (ref "U5") (pin "N7") (pinfunction "A12/~{BC}_N7") (pintype "input"))
      (node (ref "U6") (pin "N7") (pinfunction "A12/~{BC}_N7") (pintype "input"))
    )
    (net (code "23") (name "/DRAM_A13") (class "Default")
      (node (ref "R51") (pin "1") (pintype "passive"))
      (node (ref "U1") (pin "AC17") (pinfunction "DRAM_A13_AC17") (pintype "bidirectional"))
      (node (ref "U3") (pin "T3") (pinfunction "A13_T3") (pintype "input"))
      (node (ref "U4") (pin "T3") (pinfunction "A13_T3") (pintype "input"))
      (node (ref "U5") (pin "T3") (pinfunction "A13_T3") (pintype "input"))
      (node (ref "U6") (pin "T3") (pinfunction "A13_T3") (pintype "input"))
    )
    (net (code "24") (name "/DRAM_A14") (class "Default")
      (node (ref "R53") (pin "1") (pintype "passive"))
      (node (ref "U1") (pin "AA12") (pinfunction "DRAM_A14_AA12") (pintype "bidirectional"))
      (node (ref "U3") (pin "T7") (pinfunction "A14_T7") (pintype "input"))
      (node (ref "U4") (pin "T7") (pinfunction "A14_T7") (pintype "input"))
      (node (ref "U5") (pin "T7") (pinfunction "A14_T7") (pintype "input"))
      (node (ref "U6") (pin "T7") (pinfunction "A14_T7") (pintype "input"))
    )
    (net (code "25") (name "/DRAM_A15") (class "Default")
      (node (ref "R54") (pin "1") (pintype "passive"))
      (node (ref "U1") (pin "Y12") (pinfunction "DRAM_A15_Y12") (pintype "bidirectional"))
      (node (ref "U3") (pin "M7") (pinfunction "NC_(A15)_M7") (pintype "passive"))
      (node (ref "U4") (pin "M7") (pinfunction "NC_(A15)_M7") (pintype "passive"))
      (node (ref "U5") (pin "M7") (pinfunction "NC_(A15)_M7") (pintype "passive"))
      (node (ref "U6") (pin "M7") (pinfunction "NC_(A15)_M7") (pintype "passive"))
    )
    (net (code "26") (name "/DRAM_CAS_B") (class "Default")
      (node (ref "R62") (pin "1") (pintype "passive"))
      (node (ref "U1") (pin "AE16") (pinfunction "DRAM_CAS_AE16") (pintype "bidirectional"))
      (node (ref "U3") (pin "K3") (pinfunction "~{CAS}_K3") (pintype "input"))
      (node (ref "U4") (pin "K3") (pinfunction "~{CAS}_K3") (pintype "input"))
      (node (ref "U5") (pin "K3") (pinfunction "~{CAS}_K3") (pintype "input"))
      (node (ref "U6") (pin "K3") (pinfunction "~{CAS}_K3") (pintype "input"))
    )
    (net (code "27") (name "/DRAM_CLK0_CAP") (class "Default")
      (node (ref "C149") (pin "1") (pinfunction "3_1") (pintype "passive"))
      (node (ref "R52") (pin "2") (pintype "passive"))
      (node (ref "R55") (pin "2") (pintype "passive"))
    )
    (net (code "28") (name "/DRAM_CLK0_N") (class "Default")
      (node (ref "R52") (pin "1") (pintype "passive"))
      (node (ref "U1") (pin "AE15") (pinfunction "DRAM_SDCLK_0_B_AE15") (pintype "input"))
      (node (ref "U3") (pin "J7") (pinfunction "CK_J7") (pintype "input"))
      (node (ref "U4") (pin "J7") (pinfunction "CK_J7") (pintype "input"))
      (node (ref "U5") (pin "J7") (pinfunction "CK_J7") (pintype "input"))
      (node (ref "U6") (pin "J7") (pinfunction "CK_J7") (pintype "input"))
    )
    (net (code "29") (name "/DRAM_CLK0_P") (class "Default")
      (node (ref "R55") (pin "1") (pintype "passive"))
      (node (ref "U1") (pin "AD15") (pinfunction "DRAM_SDCLK_0_AD15") (pintype "input"))
      (node (ref "U3") (pin "K7") (pinfunction "~{CK}_K7") (pintype "input"))
      (node (ref "U4") (pin "K7") (pinfunction "~{CK}_K7") (pintype "input"))
      (node (ref "U5") (pin "K7") (pinfunction "~{CK}_K7") (pintype "input"))
      (node (ref "U6") (pin "K7") (pinfunction "~{CK}_K7") (pintype "input"))
    )
    (net (code "30") (name "/DRAM_CLK1_CAP") (class "Default")
      (node (ref "C176") (pin "1") (pinfunction "3_1") (pintype "passive"))
      (node (ref "R59") (pin "2") (pintype "passive"))
      (node (ref "R64") (pin "2") (pintype "passive"))
    )
    (net (code "31") (name "/DRAM_CLK1_N") (class "Default")
      (node (ref "R59") (pin "1") (pintype "passive"))
      (node (ref "U1") (pin "AE14") (pinfunction "DRAM_SDCLK_1_B_AE14") (pintype "input"))
    )
    (net (code "32") (name "/DRAM_CLK1_P") (class "Default")
      (node (ref "R64") (pin "1") (pintype "passive"))
      (node (ref "U1") (pin "AD14") (pinfunction "DRAM_SDCLK_1_AD14") (pintype "input"))
    )
    (net (code "33") (name "/DRAM_CS0_B") (class "Default")
      (node (ref "R60") (pin "1") (pintype "passive"))
      (node (ref "U1") (pin "Y16") (pinfunction "DRAM_CS0_Y16") (pintype "bidirectional"))
      (node (ref "U3") (pin "L2") (pinfunction "~{CS}_L2") (pintype "input"))
      (node (ref "U4") (pin "L2") (pinfunction "~{CS}_L2") (pintype "input"))
      (node (ref "U5") (pin "L2") (pinfunction "~{CS}_L2") (pintype "input"))
      (node (ref "U6") (pin "L2") (pinfunction "~{CS}_L2") (pintype "input"))
    )
    (net (code "34") (name "/DRAM_D0") (class "Default")
      (node (ref "U1") (pin "AD2") (pinfunction "DRAM_D0_AD2") (pintype "bidirectional"))
      (node (ref "U4") (pin "E3") (pinfunction "DQ0_E3") (pintype "bidirectional"))
    )
    (net (code "35") (name "/DRAM_D1") (class "Default")
      (node (ref "U1") (pin "AE2") (pinfunction "DRAM_D1_AE2") (pintype "bidirectional"))
      (node (ref "U4") (pin "H3") (pinfunction "DQ4_H3") (pintype "bidirectional"))
    )
    (net (code "36") (name "/DRAM_D2") (class "Default")
      (node (ref "U1") (pin "AC4") (pinfunction "DRAM_D2_AC4") (pintype "bidirectional"))
      (node (ref "U4") (pin "H7") (pinfunction "DQ7_H7") (pintype "bidirectional"))
    )
    (net (code "37") (name "/DRAM_D3") (class "Default")
      (node (ref "U1") (pin "AA5") (pinfunction "DRAM_D3_AA5") (pintype "bidirectional"))
      (node (ref "U4") (pin "F8") (pinfunction "DQ3_F8") (pintype "bidirectional"))
    )
    (net (code "38") (name "/DRAM_D4") (class "Default")
      (node (ref "U1") (pin "AC1") (pinfunction "DRAM_D4_AC1") (pintype "bidirectional"))
      (node (ref "U4") (pin "F2") (pinfunction "DQ2_F2") (pintype "bidirectional"))
    )
    (net (code "39") (name "/DRAM_D5") (class "Default")
      (node (ref "U1") (pin "AD1") (pinfunction "DRAM_D5_AD1") (pintype "bidirectional"))
      (node (ref "U4") (pin "G2") (pinfunction "DQ6_G2") (pintype "bidirectional"))
    )
    (net (code "40") (name "/DRAM_D6") (class "Default")
      (node (ref "U1") (pin "AB4") (pinfunction "DRAM_D6_AB4") (pintype "bidirectional"))
      (node (ref "U4") (pin "F7") (pinfunction "DQ1_F7") (pintype "bidirectional"))
    )
    (net (code "41") (name "/DRAM_D7") (class "Default")
      (node (ref "U1") (pin "AE4") (pinfunction "DRAM_D7_AE4") (pintype "bidirectional"))
      (node (ref "U4") (pin "H8") (pinfunction "DQ5_H8") (pintype "bidirectional"))
    )
    (net (code "42") (name "/DRAM_D8") (class "Default")
      (node (ref "U1") (pin "AD5") (pinfunction "DRAM_D8_AD5") (pintype "bidirectional"))
      (node (ref "U4") (pin "D7") (pinfunction "DQ8_D7") (pintype "bidirectional"))
    )
    (net (code "43") (name "/DRAM_D9") (class "Default")
      (node (ref "U1") (pin "AE5") (pinfunction "DRAM_D9_AE5") (pintype "bidirectional"))
      (node (ref "U4") (pin "C3") (pinfunction "DQ9_C3") (pintype "bidirectional"))
    )
    (net (code "44") (name "/DRAM_D10") (class "Default")
      (node (ref "U1") (pin "AA6") (pinfunction "DRAM_D10_AA6") (pintype "bidirectional"))
      (node (ref "U4") (pin "B8") (pinfunction "DQ14_B8") (pintype "bidirectional"))
    )
    (net (code "45") (name "/DRAM_D11") (class "Default")
      (node (ref "U1") (pin "AE7") (pinfunction "DRAM_D11_AE7") (pintype "bidirectional"))
      (node (ref "U4") (pin "C8") (pinfunction "DQ10_C8") (pintype "bidirectional"))
    )
    (net (code "46") (name "/DRAM_D12") (class "Default")
      (node (ref "U1") (pin "AB5") (pinfunction "DRAM_D12_AB5") (pintype "bidirectional"))
      (node (ref "U4") (pin "C2") (pinfunction "DQ11_C2") (pintype "bidirectional"))
    )
    (net (code "47") (name "/DRAM_D13") (class "Default")
      (node (ref "U1") (pin "AC5") (pinfunction "DRAM_D13_AC5") (pintype "bidirectional"))
      (node (ref "U4") (pin "A3") (pinfunction "DQ15_A3") (pintype "bidirectional"))
    )
    (net (code "48") (name "/DRAM_D14") (class "Default")
      (node (ref "U1") (pin "AB6") (pinfunction "DRAM_D14_AB6") (pintype "bidirectional"))
      (node (ref "U4") (pin "A2") (pinfunction "DQ13_A2") (pintype "bidirectional"))
    )
    (net (code "49") (name "/DRAM_D15") (class "Default")
      (node (ref "U1") (pin "AC7") (pinfunction "DRAM_D15_AC7") (pintype "bidirectional"))
      (node (ref "U4") (pin "A7") (pinfunction "DQ12_A7") (pintype "bidirectional"))
    )
    (net (code "50") (name "/DRAM_D16") (class "Default")
      (node (ref "U1") (pin "AB7") (pinfunction "DRAM_D16_AB7") (pintype "bidirectional"))
      (node (ref "U3") (pin "E3") (pinfunction "DQ0_E3") (pintype "bidirectional"))
    )
    (net (code "51") (name "/DRAM_D17") (class "Default")
      (node (ref "U1") (pin "AA8") (pinfunction "DRAM_D17_AA8") (pintype "bidirectional"))
      (node (ref "U3") (pin "F7") (pinfunction "DQ1_F7") (pintype "bidirectional"))
    )
    (net (code "52") (name "/DRAM_D18") (class "Default")
      (node (ref "U1") (pin "AB9") (pinfunction "DRAM_D18_AB9") (pintype "bidirectional"))
      (node (ref "U3") (pin "H3") (pinfunction "DQ4_H3") (pintype "bidirectional"))
    )
    (net (code "53") (name "/DRAM_D19") (class "Default")
      (node (ref "U1") (pin "Y9") (pinfunction "DRAM_D19_Y9") (pintype "bidirectional"))
      (node (ref "U3") (pin "H8") (pinfunction "DQ5_H8") (pintype "bidirectional"))
    )
    (net (code "54") (name "/DRAM_D20") (class "Default")
      (node (ref "U1") (pin "Y7") (pinfunction "DRAM_D20_Y7") (pintype "bidirectional"))
      (node (ref "U3") (pin "G2") (pinfunction "DQ6_G2") (pintype "bidirectional"))
    )
    (net (code "55") (name "/DRAM_D21") (class "Default")
      (node (ref "U1") (pin "Y8") (pinfunction "DRAM_D21_Y8") (pintype "bidirectional"))
      (node (ref "U3") (pin "F8") (pinfunction "DQ3_F8") (pintype "bidirectional"))
    )
    (net (code "56") (name "/DRAM_D22") (class "Default")
      (node (ref "U1") (pin "AC8") (pinfunction "DRAM_D22_AC8") (pintype "bidirectional"))
      (node (ref "U3") (pin "F2") (pinfunction "DQ2_F2") (pintype "bidirectional"))
    )
    (net (code "57") (name "/DRAM_D23") (class "Default")
      (node (ref "U1") (pin "AA9") (pinfunction "DRAM_D23_AA9") (pintype "bidirectional"))
      (node (ref "U3") (pin "H7") (pinfunction "DQ7_H7") (pintype "bidirectional"))
    )
    (net (code "58") (name "/DRAM_D24") (class "Default")
      (node (ref "U1") (pin "AE9") (pinfunction "DRAM_D24_AE9") (pintype "bidirectional"))
      (node (ref "U3") (pin "D7") (pinfunction "DQ8_D7") (pintype "bidirectional"))
    )
    (net (code "59") (name "/DRAM_D25") (class "Default")
      (node (ref "U1") (pin "Y10") (pinfunction "DRAM_D25_Y10") (pintype "bidirectional"))
      (node (ref "U3") (pin "A2") (pinfunction "DQ13_A2") (pintype "bidirectional"))
    )
    (net (code "60") (name "/DRAM_D26") (class "Default")
      (node (ref "U1") (pin "AE11") (pinfunction "DRAM_D26_AE11") (pintype "bidirectional"))
      (node (ref "U3") (pin "B8") (pinfunction "DQ14_B8") (pintype "bidirectional"))
    )
    (net (code "61") (name "/DRAM_D27") (class "Default")
      (node (ref "U1") (pin "AB11") (pinfunction "DRAM_D27_AB11") (pintype "bidirectional"))
      (node (ref "U3") (pin "C2") (pinfunction "DQ11_C2") (pintype "bidirectional"))
    )
    (net (code "62") (name "/DRAM_D28") (class "Default")
      (node (ref "U1") (pin "AC9") (pinfunction "DRAM_D28_AC9") (pintype "bidirectional"))
      (node (ref "U3") (pin "C3") (pinfunction "DQ9_C3") (pintype "bidirectional"))
    )
    (net (code "63") (name "/DRAM_D29") (class "Default")
      (node (ref "U1") (pin "AD9") (pinfunction "DRAM_D29_AD9") (pintype "bidirectional"))
      (node (ref "U3") (pin "A7") (pinfunction "DQ12_A7") (pintype "bidirectional"))
    )
    (net (code "64") (name "/DRAM_D30") (class "Default")
      (node (ref "U1") (pin "AD11") (pinfunction "DRAM_D30_AD11") (pintype "bidirectional"))
      (node (ref "U3") (pin "C8") (pinfunction "DQ10_C8") (pintype "bidirectional"))
    )
    (net (code "65") (name "/DRAM_D31") (class "Default")
      (node (ref "U1") (pin "AC11") (pinfunction "DRAM_D31_AC11") (pintype "bidirectional"))
      (node (ref "U3") (pin "A3") (pinfunction "DQ15_A3") (pintype "bidirectional"))
    )
    (net (code "66") (name "/DRAM_D32") (class "Default")
      (node (ref "U1") (pin "AA17") (pinfunction "DRAM_D32_AA17") (pintype "bidirectional"))
      (node (ref "U6") (pin "E3") (pinfunction "DQ0_E3") (pintype "bidirectional"))
    )
    (net (code "67") (name "/DRAM_D33") (class "Default")
      (node (ref "U1") (pin "AA18") (pinfunction "DRAM_D33_AA18") (pintype "bidirectional"))
      (node (ref "U6") (pin "H3") (pinfunction "DQ4_H3") (pintype "bidirectional"))
    )
    (net (code "68") (name "/DRAM_D34") (class "Default")
      (node (ref "U1") (pin "AC18") (pinfunction "DRAM_D34_AC18") (pintype "bidirectional"))
      (node (ref "U6") (pin "F7") (pinfunction "DQ1_F7") (pintype "bidirectional"))
    )
    (net (code "69") (name "/DRAM_D35") (class "Default")
      (node (ref "U1") (pin "AE19") (pinfunction "DRAM_D35_AE19") (pintype "bidirectional"))
      (node (ref "U6") (pin "H7") (pinfunction "DQ7_H7") (pintype "bidirectional"))
    )
    (net (code "70") (name "/DRAM_D36") (class "Default")
      (node (ref "U1") (pin "Y17") (pinfunction "DRAM_D36_Y17") (pintype "bidirectional"))
      (node (ref "U6") (pin "G2") (pinfunction "DQ6_G2") (pintype "bidirectional"))
    )
    (net (code "71") (name "/DRAM_D37") (class "Default")
      (node (ref "U1") (pin "Y18") (pinfunction "DRAM_D37_Y18") (pintype "bidirectional"))
      (node (ref "U6") (pin "F2") (pinfunction "DQ2_F2") (pintype "bidirectional"))
    )
    (net (code "72") (name "/DRAM_D38") (class "Default")
      (node (ref "U1") (pin "AB19") (pinfunction "DRAM_D38_AB19") (pintype "bidirectional"))
      (node (ref "U6") (pin "F8") (pinfunction "DQ3_F8") (pintype "bidirectional"))
    )
    (net (code "73") (name "/DRAM_D39") (class "Default")
      (node (ref "U1") (pin "AC19") (pinfunction "DRAM_D39_AC19") (pintype "bidirectional"))
      (node (ref "U6") (pin "H8") (pinfunction "DQ5_H8") (pintype "bidirectional"))
    )
    (net (code "74") (name "/DRAM_D40") (class "Default")
      (node (ref "U1") (pin "Y19") (pinfunction "DRAM_D40_Y19") (pintype "bidirectional"))
      (node (ref "U6") (pin "D7") (pinfunction "DQ8_D7") (pintype "bidirectional"))
    )
    (net (code "75") (name "/DRAM_D41") (class "Default")
      (node (ref "U1") (pin "AB20") (pinfunction "DRAM_D41_AB20") (pintype "bidirectional"))
      (node (ref "U6") (pin "C2") (pinfunction "DQ11_C2") (pintype "bidirectional"))
    )
    (net (code "76") (name "/DRAM_D42") (class "Default")
      (node (ref "U1") (pin "AB21") (pinfunction "DRAM_D42_AB21") (pintype "bidirectional"))
      (node (ref "U6") (pin "A7") (pinfunction "DQ12_A7") (pintype "bidirectional"))
    )
    (net (code "77") (name "/DRAM_D43") (class "Default")
      (node (ref "U1") (pin "AD21") (pinfunction "DRAM_D43_AD21") (pintype "bidirectional"))
      (node (ref "U6") (pin "C8") (pinfunction "DQ10_C8") (pintype "bidirectional"))
    )
    (net (code "78") (name "/DRAM_D44") (class "Default")
      (node (ref "U1") (pin "Y20") (pinfunction "DRAM_D44_Y20") (pintype "bidirectional"))
      (node (ref "U6") (pin "A2") (pinfunction "DQ13_A2") (pintype "bidirectional"))
    )
    (net (code "79") (name "/DRAM_D45") (class "Default")
      (node (ref "U1") (pin "AA20") (pinfunction "DRAM_D45_AA20") (pintype "bidirectional"))
      (node (ref "U6") (pin "A3") (pinfunction "DQ15_A3") (pintype "bidirectional"))
    )
    (net (code "80") (name "/DRAM_D46") (class "Default")
      (node (ref "U1") (pin "AE21") (pinfunction "DRAM_D46_AE21") (pintype "bidirectional"))
      (node (ref "U6") (pin "B8") (pinfunction "DQ14_B8") (pintype "bidirectional"))
    )
    (net (code "81") (name "/DRAM_D47") (class "Default")
      (node (ref "U1") (pin "AC21") (pinfunction "DRAM_D47_AC21") (pintype "bidirectional"))
      (node (ref "U6") (pin "C3") (pinfunction "DQ9_C3") (pintype "bidirectional"))
    )
    (net (code "82") (name "/DRAM_D48") (class "Default")
      (node (ref "U1") (pin "AC22") (pinfunction "DRAM_D48_AC22") (pintype "bidirectional"))
      (node (ref "U5") (pin "E3") (pinfunction "DQ0_E3") (pintype "bidirectional"))
    )
    (net (code "83") (name "/DRAM_D49") (class "Default")
      (node (ref "U1") (pin "AE22") (pinfunction "DRAM_D49_AE22") (pintype "bidirectional"))
      (node (ref "U5") (pin "G2") (pinfunction "DQ6_G2") (pintype "bidirectional"))
    )
    (net (code "84") (name "/DRAM_D50") (class "Default")
      (node (ref "U1") (pin "AE24") (pinfunction "DRAM_D50_AE24") (pintype "bidirectional"))
      (node (ref "U5") (pin "H7") (pinfunction "DQ7_H7") (pintype "bidirectional"))
    )
    (net (code "85") (name "/DRAM_D51") (class "Default")
      (node (ref "U1") (pin "AC24") (pinfunction "DRAM_D51_AC24") (pintype "bidirectional"))
      (node (ref "U5") (pin "F8") (pinfunction "DQ3_F8") (pintype "bidirectional"))
    )
    (net (code "86") (name "/DRAM_D52") (class "Default")
      (node (ref "U1") (pin "AB22") (pinfunction "DRAM_D52_AB22") (pintype "bidirectional"))
      (node (ref "U5") (pin "F2") (pinfunction "DQ2_F2") (pintype "bidirectional"))
    )
    (net (code "87") (name "/DRAM_D53") (class "Default")
      (node (ref "U1") (pin "AC23") (pinfunction "DRAM_D53_AC23") (pintype "bidirectional"))
      (node (ref "U5") (pin "H3") (pinfunction "DQ4_H3") (pintype "bidirectional"))
    )
    (net (code "88") (name "/DRAM_D54") (class "Default")
      (node (ref "U1") (pin "AD25") (pinfunction "DRAM_D54_AD25") (pintype "bidirectional"))
      (node (ref "U5") (pin "F7") (pinfunction "DQ1_F7") (pintype "bidirectional"))
    )
    (net (code "89") (name "/DRAM_D55") (class "Default")
      (node (ref "U1") (pin "AC25") (pinfunction "DRAM_D55_AC25") (pintype "bidirectional"))
      (node (ref "U5") (pin "H8") (pinfunction "DQ5_H8") (pintype "bidirectional"))
    )
    (net (code "90") (name "/DRAM_D56") (class "Default")
      (node (ref "U1") (pin "AB25") (pinfunction "DRAM_D56_AB25") (pintype "bidirectional"))
      (node (ref "U5") (pin "D7") (pinfunction "DQ8_D7") (pintype "bidirectional"))
    )
    (net (code "91") (name "/DRAM_D57") (class "Default")
      (node (ref "U1") (pin "AA21") (pinfunction "DRAM_D57_AA21") (pintype "bidirectional"))
      (node (ref "U5") (pin "C2") (pinfunction "DQ11_C2") (pintype "bidirectional"))
    )
    (net (code "92") (name "/DRAM_D58") (class "Default")
      (node (ref "U1") (pin "Y25") (pinfunction "DRAM_D58_Y25") (pintype "bidirectional"))
      (node (ref "U5") (pin "B8") (pinfunction "DQ14_B8") (pintype "bidirectional"))
    )
    (net (code "93") (name "/DRAM_D59") (class "Default")
      (node (ref "U1") (pin "Y22") (pinfunction "DRAM_D59_Y22") (pintype "bidirectional"))
      (node (ref "U5") (pin "A2") (pinfunction "DQ13_A2") (pintype "bidirectional"))
    )
    (net (code "94") (name "/DRAM_D60") (class "Default")
      (node (ref "U1") (pin "AB23") (pinfunction "DRAM_D60_AB23") (pintype "bidirectional"))
      (node (ref "U5") (pin "C3") (pinfunction "DQ9_C3") (pintype "bidirectional"))
    )
    (net (code "95") (name "/DRAM_D61") (class "Default")
      (node (ref "U1") (pin "AA23") (pinfunction "DRAM_D61_AA23") (pintype "bidirectional"))
      (node (ref "U5") (pin "A3") (pinfunction "DQ15_A3") (pintype "bidirectional"))
    )
    (net (code "96") (name "/DRAM_D62") (class "Default")
      (node (ref "U1") (pin "Y23") (pinfunction "DRAM_D62_Y23") (pintype "bidirectional"))
      (node (ref "U5") (pin "A7") (pinfunction "DQ12_A7") (pintype "bidirectional"))
    )
    (net (code "97") (name "/DRAM_D63") (class "Default")
      (node (ref "U1") (pin "W25") (pinfunction "DRAM_D63_W25") (pintype "bidirectional"))
      (node (ref "U5") (pin "C8") (pinfunction "DQ10_C8") (pintype "bidirectional"))
    )
    (net (code "98") (name "/DRAM_DQM0") (class "Default")
      (node (ref "U1") (pin "AC3") (pinfunction "DRAM_DQM0_AC3") (pintype "bidirectional"))
      (node (ref "U4") (pin "E7") (pinfunction "LDM_E7") (pintype "input"))
    )
    (net (code "99") (name "/DRAM_DQM1") (class "Default")
      (node (ref "U1") (pin "AC6") (pinfunction "DRAM_DQM1_AC6") (pintype "bidirectional"))
      (node (ref "U4") (pin "D3") (pinfunction "UDM_D3") (pintype "input"))
    )
    (net (code "100") (name "/DRAM_DQM2") (class "Default")
      (node (ref "U1") (pin "AB8") (pinfunction "DRAM_DQM2_AB8") (pintype "bidirectional"))
      (node (ref "U3") (pin "E7") (pinfunction "LDM_E7") (pintype "input"))
    )
    (net (code "101") (name "/DRAM_DQM3") (class "Default")
      (node (ref "U1") (pin "AE10") (pinfunction "DRAM_DQM3_AE10") (pintype "bidirectional"))
      (node (ref "U3") (pin "D3") (pinfunction "UDM_D3") (pintype "input"))
    )
    (net (code "102") (name "/DRAM_DQM4") (class "Default")
      (node (ref "U1") (pin "AB18") (pinfunction "DRAM_DQM4_AB18") (pintype "bidirectional"))
      (node (ref "U6") (pin "E7") (pinfunction "LDM_E7") (pintype "input"))
    )
    (net (code "103") (name "/DRAM_DQM5") (class "Default")
      (node (ref "U1") (pin "AC20") (pinfunction "DRAM_DQM5_AC20") (pintype "bidirectional"))
      (node (ref "U6") (pin "D3") (pinfunction "UDM_D3") (pintype "input"))
    )
    (net (code "104") (name "/DRAM_DQM6") (class "Default")
      (node (ref "U1") (pin "AD24") (pinfunction "DRAM_DQM6_AD24") (pintype "bidirectional"))
      (node (ref "U5") (pin "E7") (pinfunction "LDM_E7") (pintype "input"))
    )
    (net (code "105") (name "/DRAM_DQM7") (class "Default")
      (node (ref "U1") (pin "Y21") (pinfunction "DRAM_DQM7_Y21") (pintype "bidirectional"))
      (node (ref "U5") (pin "D3") (pinfunction "UDM_D3") (pintype "input"))
    )
    (net (code "106") (name "/DRAM_DQS0_N") (class "Default")
      (node (ref "U1") (pin "AD3") (pinfunction "DRAM_SDQS0_B_AD3") (pintype "bidirectional"))
      (node (ref "U4") (pin "G3") (pinfunction "~{LDQS}_G3") (pintype "bidirectional"))
    )
    (net (code "107") (name "/DRAM_DQS0_P") (class "Default")
      (node (ref "U1") (pin "AE3") (pinfunction "DRAM_SDQS0_AE3") (pintype "bidirectional"))
      (node (ref "U4") (pin "F3") (pinfunction "LDQS_F3") (pintype "bidirectional"))
    )
    (net (code "108") (name "/DRAM_DQS1_N") (class "Default")
      (node (ref "U1") (pin "AE6") (pinfunction "DRAM_SDQS1_B_AE6") (pintype "bidirectional"))
      (node (ref "U4") (pin "B7") (pinfunction "~{UDQS}_B7") (pintype "bidirectional"))
    )
    (net (code "109") (name "/DRAM_DQS1_P") (class "Default")
      (node (ref "U1") (pin "AD6") (pinfunction "DRAM_SDQS1_AD6") (pintype "bidirectional"))
      (node (ref "U4") (pin "C7") (pinfunction "UDQS_C7") (pintype "bidirectional"))
    )
    (net (code "110") (name "/DRAM_DQS2_N") (class "Default")
      (node (ref "U1") (pin "AE8") (pinfunction "DRAM_SDQS2_B_AE8") (pintype "bidirectional"))
      (node (ref "U3") (pin "G3") (pinfunction "~{LDQS}_G3") (pintype "bidirectional"))
    )
    (net (code "111") (name "/DRAM_DQS2_P") (class "Default")
      (node (ref "U1") (pin "AD8") (pinfunction "DRAM_SDQS2_AD8") (pintype "bidirectional"))
      (node (ref "U3") (pin "F3") (pinfunction "LDQS_F3") (pintype "bidirectional"))
    )
    (net (code "112") (name "/DRAM_DQS3_N") (class "Default")
      (node (ref "U1") (pin "AB10") (pinfunction "DRAM_SDQS3_B_AB10") (pintype "bidirectional"))
      (node (ref "U3") (pin "B7") (pinfunction "~{UDQS}_B7") (pintype "bidirectional"))
    )
    (net (code "113") (name "/DRAM_DQS3_P") (class "Default")
      (node (ref "U1") (pin "AC10") (pinfunction "DRAM_SDQS3_AC10") (pintype "bidirectional"))
      (node (ref "U3") (pin "C7") (pinfunction "UDQS_C7") (pintype "bidirectional"))
    )
    (net (code "114") (name "/DRAM_DQS4_N") (class "Default")
      (node (ref "U1") (pin "AE18") (pinfunction "DRAM_SDQS4_B_AE18") (pintype "bidirectional"))
      (node (ref "U6") (pin "G3") (pinfunction "~{LDQS}_G3") (pintype "bidirectional"))
    )
    (net (code "115") (name "/DRAM_DQS4_P") (class "Default")
      (node (ref "U1") (pin "AD18") (pinfunction "DRAM_SDQS4_AD18") (pintype "bidirectional"))
      (node (ref "U6") (pin "F3") (pinfunction "LDQS_F3") (pintype "bidirectional"))
    )
    (net (code "116") (name "/DRAM_DQS5_N") (class "Default")
      (node (ref "U1") (pin "AE20") (pinfunction "DRAM_SDQS5_B_AE20") (pintype "bidirectional"))
      (node (ref "U6") (pin "B7") (pinfunction "~{UDQS}_B7") (pintype "bidirectional"))
    )
    (net (code "117") (name "/DRAM_DQS5_P") (class "Default")
      (node (ref "U1") (pin "AD20") (pinfunction "DRAM_SDQS5_AD20") (pintype "bidirectional"))
      (node (ref "U6") (pin "C7") (pinfunction "UDQS_C7") (pintype "bidirectional"))
    )
    (net (code "118") (name "/DRAM_DQS6_N") (class "Default")
      (node (ref "U1") (pin "AE23") (pinfunction "DRAM_SDQS6_B_AE23") (pintype "bidirectional"))
      (node (ref "U5") (pin "G3") (pinfunction "~{LDQS}_G3") (pintype "bidirectional"))
    )
    (net (code "119") (name "/DRAM_DQS6_P") (class "Default")
      (node (ref "U1") (pin "AD23") (pinfunction "DRAM_SDQS6_AD23") (pintype "bidirectional"))
      (node (ref "U5") (pin "F3") (pinfunction "LDQS_F3") (pintype "bidirectional"))
    )
    (net (code "120") (name "/DRAM_DQS7_N") (class "Default")
      (node (ref "U1") (pin "AA24") (pinfunction "DRAM_SDQS7_B_AA24") (pintype "bidirectional"))
      (node (ref "U5") (pin "B7") (pinfunction "~{UDQS}_B7") (pintype "bidirectional"))
    )
    (net (code "121") (name "/DRAM_DQS7_P") (class "Default")
      (node (ref "U1") (pin "AA25") (pinfunction "DRAM_SDQS7_AA25") (pintype "bidirectional"))
      (node (ref "U5") (pin "C7") (pinfunction "UDQS_C7") (pintype "bidirectional"))
    )
    (net (code "122") (name "/DRAM_RAS_B") (class "Default")
      (node (ref "R61") (pin "1") (pintype "passive"))
      (node (ref "U1") (pin "AB15") (pinfunction "DRAM_RAS_AB15") (pintype "bidirectional"))
      (node (ref "U3") (pin "J3") (pinfunction "~{RAS}_J3") (pintype "input"))
      (node (ref "U4") (pin "J3") (pinfunction "~{RAS}_J3") (pintype "input"))
      (node (ref "U5") (pin "J3") (pinfunction "~{RAS}_J3") (pintype "input"))
      (node (ref "U6") (pin "J3") (pinfunction "~{RAS}_J3") (pintype "input"))
    )
    (net (code "123") (name "/DRAM_RESET_B") (class "Default")
      (node (ref "R32") (pin "2") (pintype "passive"))
      (node (ref "U1") (pin "Y6") (pinfunction "DRAM_RESET_Y6") (pintype "bidirectional"))
      (node (ref "U3") (pin "T2") (pinfunction "~{RESET}_T2") (pintype "input"))
      (node (ref "U4") (pin "T2") (pinfunction "~{RESET}_T2") (pintype "input"))
      (node (ref "U5") (pin "T2") (pinfunction "~{RESET}_T2") (pintype "input"))
      (node (ref "U6") (pin "T2") (pinfunction "~{RESET}_T2") (pintype "input"))
    )
    (net (code "124") (name "/DRAM_SDBA0") (class "Default")
      (node (ref "R56") (pin "1") (pintype "passive"))
      (node (ref "U1") (pin "AC15") (pinfunction "DRAM_SDBA0_AC15") (pintype "bidirectional"))
      (node (ref "U3") (pin "M2") (pinfunction "BA0_M2") (pintype "input"))
      (node (ref "U4") (pin "M2") (pinfunction "BA0_M2") (pintype "input"))
      (node (ref "U5") (pin "M2") (pinfunction "BA0_M2") (pintype "input"))
      (node (ref "U6") (pin "M2") (pinfunction "BA0_M2") (pintype "input"))
    )
    (net (code "125") (name "/DRAM_SDBA1") (class "Default")
      (node (ref "R57") (pin "1") (pintype "passive"))
      (node (ref "U1") (pin "Y15") (pinfunction "DRAM_SDBA1_Y15") (pintype "bidirectional"))
      (node (ref "U3") (pin "N8") (pinfunction "BA1_N8") (pintype "input"))
      (node (ref "U4") (pin "N8") (pinfunction "BA1_N8") (pintype "input"))
      (node (ref "U5") (pin "N8") (pinfunction "BA1_N8") (pintype "input"))
      (node (ref "U6") (pin "N8") (pinfunction "BA1_N8") (pintype "input"))
    )
    (net (code "126") (name "/DRAM_SDBA2") (class "Default")
      (node (ref "R58") (pin "1") (pintype "passive"))
      (node (ref "U1") (pin "AB12") (pinfunction "DRAM_SDBA2_AB12") (pintype "bidirectional"))
      (node (ref "U3") (pin "M3") (pinfunction "BA2_M3") (pintype "input"))
      (node (ref "U4") (pin "M3") (pinfunction "BA2_M3") (pintype "input"))
      (node (ref "U5") (pin "M3") (pinfunction "BA2_M3") (pintype "input"))
      (node (ref "U6") (pin "M3") (pinfunction "BA2_M3") (pintype "input"))
    )
    (net (code "127") (name "/DRAM_SDCKE0") (class "Default")
      (node (ref "R31") (pin "2") (pintype "passive"))
      (node (ref "R65") (pin "1") (pintype "passive"))
      (node (ref "U1") (pin "Y11") (pinfunction "DRAM_SDCKE0_Y11") (pintype "passive"))
      (node (ref "U3") (pin "K9") (pinfunction "CKE_K9") (pintype "input"))
      (node (ref "U4") (pin "K9") (pinfunction "CKE_K9") (pintype "input"))
      (node (ref "U5") (pin "K9") (pinfunction "CKE_K9") (pintype "input"))
      (node (ref "U6") (pin "K9") (pinfunction "CKE_K9") (pintype "input"))
    )
    (net (code "128") (name "/DRAM_SDODT0") (class "Default")
      (node (ref "R66") (pin "1") (pintype "passive"))
      (node (ref "U1") (pin "AC16") (pinfunction "DRAM_SDODT0_AC16") (pintype "passive"))
      (node (ref "U3") (pin "K1") (pinfunction "ODT_K1") (pintype "input"))
      (node (ref "U4") (pin "K1") (pinfunction "ODT_K1") (pintype "input"))
      (node (ref "U5") (pin "K1") (pinfunction "ODT_K1") (pintype "input"))
      (node (ref "U6") (pin "K1") (pinfunction "ODT_K1") (pintype "input"))
    )
    (net (code "129") (name "/DRAM_WE_B") (class "Default")
      (node (ref "R63") (pin "1") (pintype "passive"))
      (node (ref "U1") (pin "AB16") (pinfunction "DRAM_SDWE_AB16") (pintype "bidirectional"))
      (node (ref "U3") (pin "L3") (pinfunction "~{WE}_L3") (pintype "input"))
      (node (ref "U4") (pin "L3") (pinfunction "~{WE}_L3") (pintype "input"))
      (node (ref "U5") (pin "L3") (pinfunction "~{WE}_L3") (pintype "input"))
      (node (ref "U6") (pin "L3") (pinfunction "~{WE}_L3") (pintype "input"))
    )
    (net (code "130") (name "/ZQPAD") (class "Default")
      (node (ref "R35") (pin "2") (pintype "passive"))
      (node (ref "U1") (pin "AE17") (pinfunction "ZQPAD_AE17") (pintype "passive"))
    )
    (net (code "133") (name "GND") (class "Default")
      (node (ref "C105") (pin "2") (pinfunction "4_2") (pintype "passive"))
      (node (ref "C106") (pin "2") (pinfunction "4_2") (pintype "passive"))
      (node (ref "C107") (pin "2") (pinfunction "4_2") (pintype "passive"))
      (node (ref "C108") (pin "2") (pinfunction "4_2") (pintype "passive"))
      (node (ref "C109") (pin "2") (pinfunction "4_2") (pintype "passive"))
      (node (ref "C110") (pin "2") (pinfunction "4_2") (pintype "passive"))
      (node (ref "C111") (pin "2") (pinfunction "4_2") (pintype "passive"))
      (node (ref "C112") (pin "2") (pinfunction "4_2") (pintype "passive"))
      (node (ref "C113") (pin "2") (pinfunction "4_2") (pintype "passive"))
      (node (ref "C114") (pin "2") (pinfunction "4_2") (pintype "passive"))
      (node (ref "C115") (pin "2") (pinfunction "4_2") (pintype "passive"))
      (node (ref "C116") (pin "2") (pinfunction "4_2") (pintype "passive"))
      (node (ref "C117") (pin "2") (pinfunction "4_2") (pintype "passive"))
      (node (ref "C118") (pin "2") (pinfunction "4_2") (pintype "passive"))
      (node (ref "C119") (pin "2") (pinfunction "4_2") (pintype "passive"))
      (node (ref "C120") (pin "2") (pinfunction "4_2") (pintype "passive"))
      (node (ref "C121") (pin "2") (pinfunction "4_2") (pintype "passive"))
      (node (ref "C122") (pin "2") (pinfunction "4_2") (pintype "passive"))
      (node (ref "C123") (pin "2") (pinfunction "4_2") (pintype "passive"))
      (node (ref "C124") (pin "2") (pinfunction "4_2") (pintype "passive"))
      (node (ref "C125") (pin "2") (pinfunction "4_2") (pintype "passive"))
      (node (ref "C126") (pin "2") (pinfunction "4_2") (pintype "passive"))
      (node (ref "C127") (pin "2") (pinfunction "4_2") (pintype "passive"))
      (node (ref "C128") (pin "2") (pinfunction "4_2") (pintype "passive"))
      (node (ref "C129") (pin "2") (pinfunction "4_2") (pintype "passive"))
      (node (ref "C130") (pin "2") (pinfunction "4_2") (pintype "passive"))
      (node (ref "C131") (pin "2") (pinfunction "4_2") (pintype "passive"))
      (node (ref "C132") (pin "2") (pinfunction "4_2") (pintype "passive"))
      (node (ref "C133") (pin "2") (pinfunction "4_2") (pintype "passive"))
      (node (ref "C134") (pin "2") (pinfunction "4_2") (pintype "passive"))
      (node (ref "C135") (pin "2") (pinfunction "4_2") (pintype "passive"))
      (node (ref "C136") (pin "2") (pinfunction "4_2") (pintype "passive"))
      (node (ref "C137") (pin "2") (pinfunction "4_2") (pintype "passive"))
      (node (ref "C138") (pin "2") (pinfunction "4_2") (pintype "passive"))
      (node (ref "C139") (pin "2") (pinfunction "4_2") (pintype "passive"))
      (node (ref "C140") (pin "2") (pinfunction "4_2") (pintype "passive"))
      (node (ref "C141") (pin "2") (pinfunction "4_2") (pintype "passive"))
      (node (ref "C142") (pin "2") (pinfunction "4_2") (pintype "passive"))
      (node (ref "C143") (pin "2") (pinfunction "4_2") (pintype "passive"))
      (node (ref "C144") (pin "2") (pinfunction "4_2") (pintype "passive"))
      (node (ref "C145") (pin "2") (pinfunction "4_2") (pintype "passive"))
      (node (ref "C146") (pin "2") (pinfunction "4_2") (pintype "passive"))
      (node (ref "C147") (pin "2") (pinfunction "4_2") (pintype "passive"))
      (node (ref "C148") (pin "2") (pinfunction "4_2") (pintype "passive"))
      (node (ref "C150") (pin "2") (pinfunction "4_2") (pintype "passive"))
      (node (ref "C151") (pin "2") (pinfunction "4_2") (pintype "passive"))
      (node (ref "C152") (pin "2") (pinfunction "4_2") (pintype "passive"))
      (node (ref "C153") (pin "2") (pinfunction "4_2") (pintype "passive"))
      (node (ref "C154") (pin "2") (pinfunction "4_2") (pintype "passive"))
      (node (ref "C155") (pin "2") (pinfunction "4_2") (pintype "passive"))
      (node (ref "C156") (pin "2") (pinfunction "4_2") (pintype "passive"))
      (node (ref "C157") (pin "2") (pinfunction "4_2") (pintype "passive"))
      (node (ref "C158") (pin "2") (pinfunction "4_2") (pintype "passive"))
      (node (ref "C159") (pin "2") (pinfunction "4_2") (pintype "passive"))
      (node (ref "C160") (pin "2") (pinfunction "4_2") (pintype "passive"))
      (node (ref "C161") (pin "2") (pinfunction "4_2") (pintype "passive"))
      (node (ref "C162") (pin "2") (pinfunction "4_2") (pintype "passive"))
      (node (ref "C163") (pin "2") (pinfunction "4_2") (pintype "passive"))
      (node (ref "C164") (pin "2") (pinfunction "4_2") (pintype "passive"))
      (node (ref "C165") (pin "2") (pinfunction "4_2") (pintype "passive"))
      (node (ref "C166") (pin "2") (pinfunction "4_2") (pintype "passive"))
      (node (ref "C167") (pin "2") (pinfunction "4_2") (pintype "passive"))
      (node (ref "C168") (pin "2") (pinfunction "4_2") (pintype "passive"))
      (node (ref "C169") (pin "2") (pinfunction "4_2") (pintype "passive"))
      (node (ref "C170") (pin "2") (pinfunction "4_2") (pintype "passive"))
      (node (ref "C171") (pin "2") (pinfunction "4_2") (pintype "passive"))
      (node (ref "C172") (pin "2") (pinfunction "4_2") (pintype "passive"))
      (node (ref "C173") (pin "2") (pinfunction "4_2") (pintype "passive"))
      (node (ref "C174") (pin "2") (pinfunction "4_2") (pintype "passive"))
      (node (ref "C175") (pin "2") (pinfunction "4_2") (pintype "passive"))
      (node (ref "R27") (pin "1") (pintype "passive"))
      (node (ref "R28") (pin "1") (pintype "passive"))
      (node (ref "R29") (pin "1") (pintype "passive"))
      (node (ref "R30") (pin "1") (pintype "passive"))
      (node (ref "R31") (pin "1") (pintype "passive"))
      (node (ref "R32") (pin "1") (pintype "passive"))
      (node (ref "R33") (pin "1") (pintype "passive"))
      (node (ref "R34") (pin "1") (pintype "passive"))
      (node (ref "R35") (pin "1") (pintype "passive"))
      (node (ref "R36") (pin "1") (pintype "passive"))
      (node (ref "R37") (pin "1") (pintype "passive"))
      (node (ref "U3") (pin "A9") (pinfunction "VSS_A9") (pintype "power_in"))
      (node (ref "U3") (pin "B1") (pinfunction "VSSQ_B1") (pintype "power_in"))
      (node (ref "U3") (pin "B3") (pinfunction "VSS_B3") (pintype "power_in"))
      (node (ref "U3") (pin "B9") (pinfunction "VSSQ_B9") (pintype "power_in"))
      (node (ref "U3") (pin "D1") (pinfunction "VSSQ_D1") (pintype "power_in"))
      (node (ref "U3") (pin "D8") (pinfunction "VSSQ_D8") (pintype "power_in"))
      (node (ref "U3") (pin "E1") (pinfunction "VSS_E1") (pintype "power_in"))
      (node (ref "U3") (pin "E2") (pinfunction "VSSQ_E2") (pintype "power_in"))
      (node (ref "U3") (pin "E8") (pinfunction "VSSQ_E8") (pintype "power_in"))
      (node (ref "U3") (pin "F9") (pinfunction "VSSQ_F9") (pintype "power_in"))
      (node (ref "U3") (pin "G1") (pinfunction "VSSQ_G1") (pintype "power_in"))
      (node (ref "U3") (pin "G8") (pinfunction "VSS_G8") (pintype "power_in"))
      (node (ref "U3") (pin "G9") (pinfunction "VSSQ_G9") (pintype "power_in"))
      (node (ref "U3") (pin "J2") (pinfunction "VSS_J2") (pintype "power_in"))
      (node (ref "U3") (pin "J8") (pinfunction "VSS_J8") (pintype "power_in"))
      (node (ref "U3") (pin "M1") (pinfunction "VSS_M1") (pintype "power_in"))
      (node (ref "U3") (pin "M9") (pinfunction "VSS_M9") (pintype "power_in"))
      (node (ref "U3") (pin "P1") (pinfunction "VSS_P1") (pintype "power_in"))
      (node (ref "U3") (pin "P9") (pinfunction "VSS_P9") (pintype "power_in"))
      (node (ref "U3") (pin "T1") (pinfunction "VSS_T1") (pintype "power_in"))
      (node (ref "U3") (pin "T9") (pinfunction "VSS_T9") (pintype "power_in"))
      (node (ref "U4") (pin "A9") (pinfunction "VSS_A9") (pintype "power_in"))
      (node (ref "U4") (pin "B1") (pinfunction "VSSQ_B1") (pintype "power_in"))
      (node (ref "U4") (pin "B3") (pinfunction "VSS_B3") (pintype "power_in"))
      (node (ref "U4") (pin "B9") (pinfunction "VSSQ_B9") (pintype "power_in"))
      (node (ref "U4") (pin "D1") (pinfunction "VSSQ_D1") (pintype "power_in"))
      (node (ref "U4") (pin "D8") (pinfunction "VSSQ_D8") (pintype "power_in"))
      (node (ref "U4") (pin "E1") (pinfunction "VSS_E1") (pintype "power_in"))
      (node (ref "U4") (pin "E2") (pinfunction "VSSQ_E2") (pintype "power_in"))
      (node (ref "U4") (pin "E8") (pinfunction "VSSQ_E8") (pintype "power_in"))
      (node (ref "U4") (pin "F9") (pinfunction "VSSQ_F9") (pintype "power_in"))
      (node (ref "U4") (pin "G1") (pinfunction "VSSQ_G1") (pintype "power_in"))
      (node (ref "U4") (pin "G8") (pinfunction "VSS_G8") (pintype "power_in"))
      (node (ref "U4") (pin "G9") (pinfunction "VSSQ_G9") (pintype "power_in"))
      (node (ref "U4") (pin "J2") (pinfunction "VSS_J2") (pintype "power_in"))
      (node (ref "U4") (pin "J8") (pinfunction "VSS_J8") (pintype "power_in"))
      (node (ref "U4") (pin "M1") (pinfunction "VSS_M1") (pintype "power_in"))
      (node (ref "U4") (pin "M9") (pinfunction "VSS_M9") (pintype "power_in"))
      (node (ref "U4") (pin "P1") (pinfunction "VSS_P1") (pintype "power_in"))
      (node (ref "U4") (pin "P9") (pinfunction "VSS_P9") (pintype "power_in"))
      (node (ref "U4") (pin "T1") (pinfunction "VSS_T1") (pintype "power_in"))
      (node (ref "U4") (pin "T9") (pinfunction "VSS_T9") (pintype "power_in"))
      (node (ref "U5") (pin "A9") (pinfunction "VSS_A9") (pintype "power_in"))
      (node (ref "U5") (pin "B1") (pinfunction "VSSQ_B1") (pintype "power_in"))
      (node (ref "U5") (pin "B3") (pinfunction "VSS_B3") (pintype "power_in"))
      (node (ref "U5") (pin "B9") (pinfunction "VSSQ_B9") (pintype "power_in"))
      (node (ref "U5") (pin "D1") (pinfunction "VSSQ_D1") (pintype "power_in"))
      (node (ref "U5") (pin "D8") (pinfunction "VSSQ_D8") (pintype "power_in"))
      (node (ref "U5") (pin "E1") (pinfunction "VSS_E1") (pintype "power_in"))
      (node (ref "U5") (pin "E2") (pinfunction "VSSQ_E2") (pintype "power_in"))
      (node (ref "U5") (pin "E8") (pinfunction "VSSQ_E8") (pintype "power_in"))
      (node (ref "U5") (pin "F9") (pinfunction "VSSQ_F9") (pintype "power_in"))
      (node (ref "U5") (pin "G1") (pinfunction "VSSQ_G1") (pintype "power_in"))
      (node (ref "U5") (pin "G8") (pinfunction "VSS_G8") (pintype "power_in"))
      (node (ref "U5") (pin "G9") (pinfunction "VSSQ_G9") (pintype "power_in"))
      (node (ref "U5") (pin "J2") (pinfunction "VSS_J2") (pintype "power_in"))
      (node (ref "U5") (pin "J8") (pinfunction "VSS_J8") (pintype "power_in"))
      (node (ref "U5") (pin "M1") (pinfunction "VSS_M1") (pintype "power_in"))
      (node (ref "U5") (pin "M9") (pinfunction "VSS_M9") (pintype "power_in"))
      (node (ref "U5") (pin "P1") (pinfunction "VSS_P1") (pintype "power_in"))
      (node (ref "U5") (pin "P9") (pinfunction "VSS_P9") (pintype "power_in"))
      (node (ref "U5") (pin "T1") (pinfunction "VSS_T1") (pintype "power_in"))
      (node (ref "U5") (pin "T9") (pinfunction "VSS_T9") (pintype "power_in"))
      (node (ref "U6") (pin "A9") (pinfunction "VSS_A9") (pintype "power_in"))
      (node (ref "U6") (pin "B1") (pinfunction "VSSQ_B1") (pintype "power_in"))
      (node (ref "U6") (pin "B3") (pinfunction "VSS_B3") (pintype "power_in"))
      (node (ref "U6") (pin "B9") (pinfunction "VSSQ_B9") (pintype "power_in"))
      (node (ref "U6") (pin "D1") (pinfunction "VSSQ_D1") (pintype "power_in"))
      (node (ref "U6") (pin "D8") (pinfunction "VSSQ_D8") (pintype "power_in"))
      (node (ref "U6") (pin "E1") (pinfunction "VSS_E1") (pintype "power_in"))
      (node (ref "U6") (pin "E2") (pinfunction "VSSQ_E2") (pintype "power_in"))
      (node (ref "U6") (pin "E8") (pinfunction "VSSQ_E8") (pintype "power_in"))
      (node (ref "U6") (pin "F9") (pinfunction "VSSQ_F9") (pintype "power_in"))
      (node (ref "U6") (pin "G1") (pinfunction "VSSQ_G1") (pintype "power_in"))
      (node (ref "U6") (pin "G8") (pinfunction "VSS_G8") (pintype "power_in"))
      (node (ref "U6") (pin "G9") (pinfunction "VSSQ_G9") (pintype "power_in"))
      (node (ref "U6") (pin "J2") (pinfunction "VSS_J2") (pintype "power_in"))
      (node (ref "U6") (pin "J8") (pinfunction "VSS_J8") (pintype "power_in"))
      (node (ref "U6") (pin "M1") (pinfunction "VSS_M1") (pintype "power_in"))
      (node (ref "U6") (pin "M9") (pinfunction "VSS_M9") (pintype "power_in"))
      (node (ref "U6") (pin "P1") (pinfunction "VSS_P1") (pintype "power_in"))
      (node (ref "U6") (pin "P9") (pinfunction "VSS_P9") (pintype "power_in"))
      (node (ref "U6") (pin "T1") (pinfunction "VSS_T1") (pintype "power_in"))
      (node (ref "U6") (pin "T9") (pinfunction "VSS_T9") (pintype "power_in"))
    )
    (net (code "134") (name "Net-(R27-Pad2)") (class "Default")
      (node (ref "R27") (pin "2") (pintype "passive"))
      (node (ref "U3") (pin "L9") (pinfunction "NC_L9") (pintype "passive"))
    )
    (net (code "135") (name "Net-(R28-Pad2)") (class "Default")
      (node (ref "R28") (pin "2") (pintype "passive"))
      (node (ref "U4") (pin "L9") (pinfunction "NC_L9") (pintype "passive"))
    )
    (net (code "136") (name "Net-(R33-Pad2)") (class "Default")
      (node (ref "R33") (pin "2") (pintype "passive"))
      (node (ref "U5") (pin "L9") (pinfunction "NC_L9") (pintype "passive"))
    )
    (net (code "137") (name "Net-(R34-Pad2)") (class "Default")
      (node (ref "R34") (pin "2") (pintype "passive"))
      (node (ref "U6") (pin "L9") (pinfunction "NC_L9") (pintype "passive"))
    )
    (net (code "138") (name "unconnected-(U1B-DRAM_CS1-PadAD17)") (class "Default")
      (node (ref "U1") (pin "AD17") (pinfunction "DRAM_CS1_AD17") (pintype "bidirectional+no_connect"))
    )
    (net (code "139") (name "unconnected-(U1B-DRAM_SDCKE1-PadAA11)") (class "Default")
      (node (ref "U1") (pin "AA11") (pinfunction "DRAM_SDCKE1_AA11") (pintype "passive+no_connect"))
    )
    (net (code "140") (name "unconnected-(U1B-DRAM_SDODT1-PadAB17)") (class "Default")
      (node (ref "U1") (pin "AB17") (pinfunction "DRAM_SDODT1_AB17") (pintype "passive+no_connect"))
    )
    (net (code "141") (name "unconnected-(U3-NC-PadJ1)") (class "Default")
      (node (ref "U3") (pin "J1") (pinfunction "NC_J1") (pintype "passive+no_connect"))
    )
    (net (code "142") (name "unconnected-(U3-NC-PadJ9)") (class "Default")
      (node (ref "U3") (pin "J9") (pinfunction "NC_J9") (pintype "passive+no_connect"))
    )
    (net (code "143") (name "unconnected-(U3-NC-PadL1)") (class "Default")
      (node (ref "U3") (pin "L1") (pinfunction "NC_L1") (pintype "passive+no_connect"))
    )
    (net (code "144") (name "unconnected-(U4-NC-PadJ1)") (class "Default")
      (node (ref "U4") (pin "J1") (pinfunction "NC_J1") (pintype "passive+no_connect"))
    )
    (net (code "145") (name "unconnected-(U4-NC-PadJ9)") (class "Default")
      (node (ref "U4") (pin "J9") (pinfunction "NC_J9") (pintype "passive+no_connect"))
    )
    (net (code "146") (name "unconnected-(U4-NC-PadL1)") (class "Default")
      (node (ref "U4") (pin "L1") (pinfunction "NC_L1") (pintype "passive+no_connect"))
    )
    (net (code "147") (name "unconnected-(U5-NC-PadJ1)") (class "Default")
      (node (ref "U5") (pin "J1") (pinfunction "NC_J1") (pintype "passive+no_connect"))
    )
    (net (code "148") (name "unconnected-(U5-NC-PadJ9)") (class "Default")
      (node (ref "U5") (pin "J9") (pinfunction "NC_J9") (pintype "passive+no_connect"))
    )
    (net (code "149") (name "unconnected-(U5-NC-PadL1)") (class "Default")
      (node (ref "U5") (pin "L1") (pinfunction "NC_L1") (pintype "passive+no_connect"))
    )
    (net (code "150") (name "unconnected-(U6-NC-PadJ1)") (class "Default")
      (node (ref "U6") (pin "J1") (pinfunction "NC_J1") (pintype "passive+no_connect"))
    )
    (net (code "151") (name "unconnected-(U6-NC-PadJ9)") (class "Default")
      (node (ref "U6") (pin "J9") (pinfunction "NC_J9") (pintype "passive+no_connect"))
    )
    (net (code "152") (name "unconnected-(U6-NC-PadL1)") (class "Default")
      (node (ref "U6") (pin "L1") (pinfunction "NC_L1") (pintype "passive+no_connect"))
    )
  )
)
